# 4G_AD9.net
KiCad netlist of a schematic drawn in Altium Designer
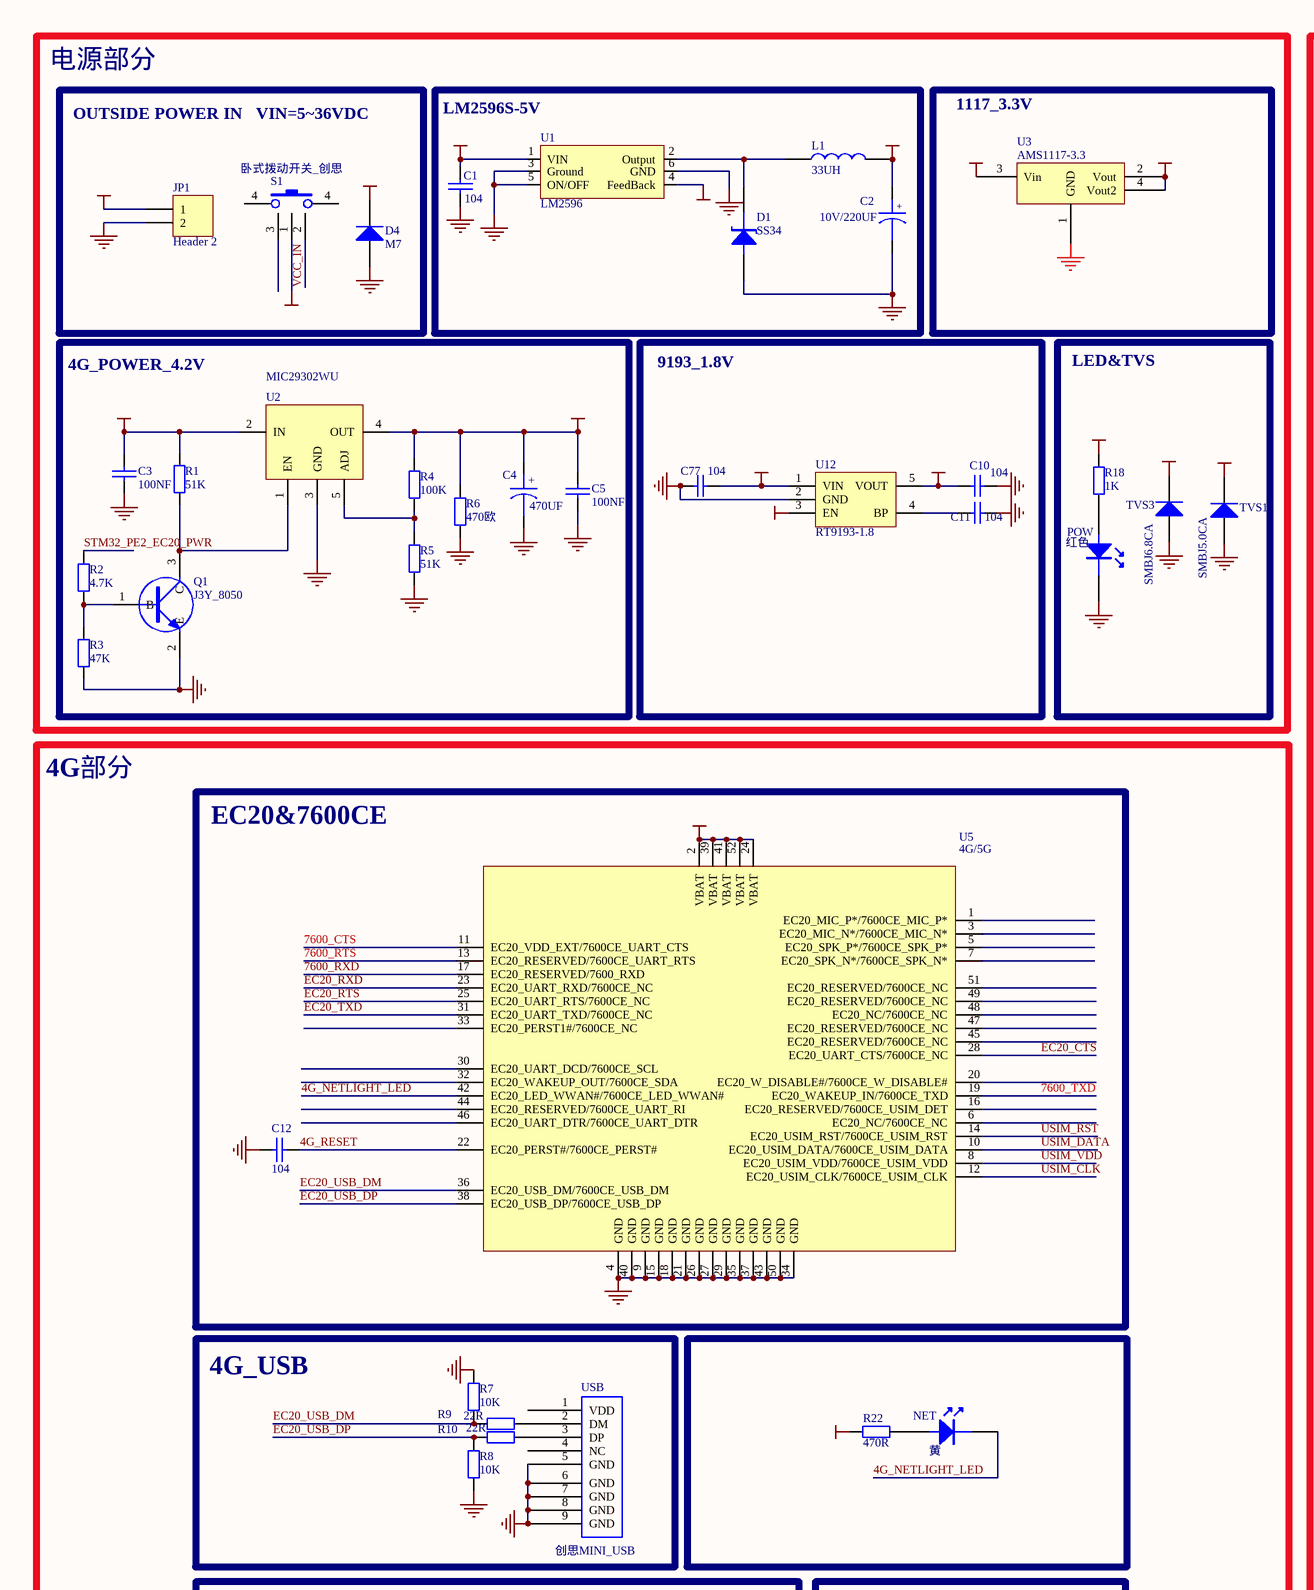
[diagram p0: 4G图传输原理图AD9.SchDoc, top left]
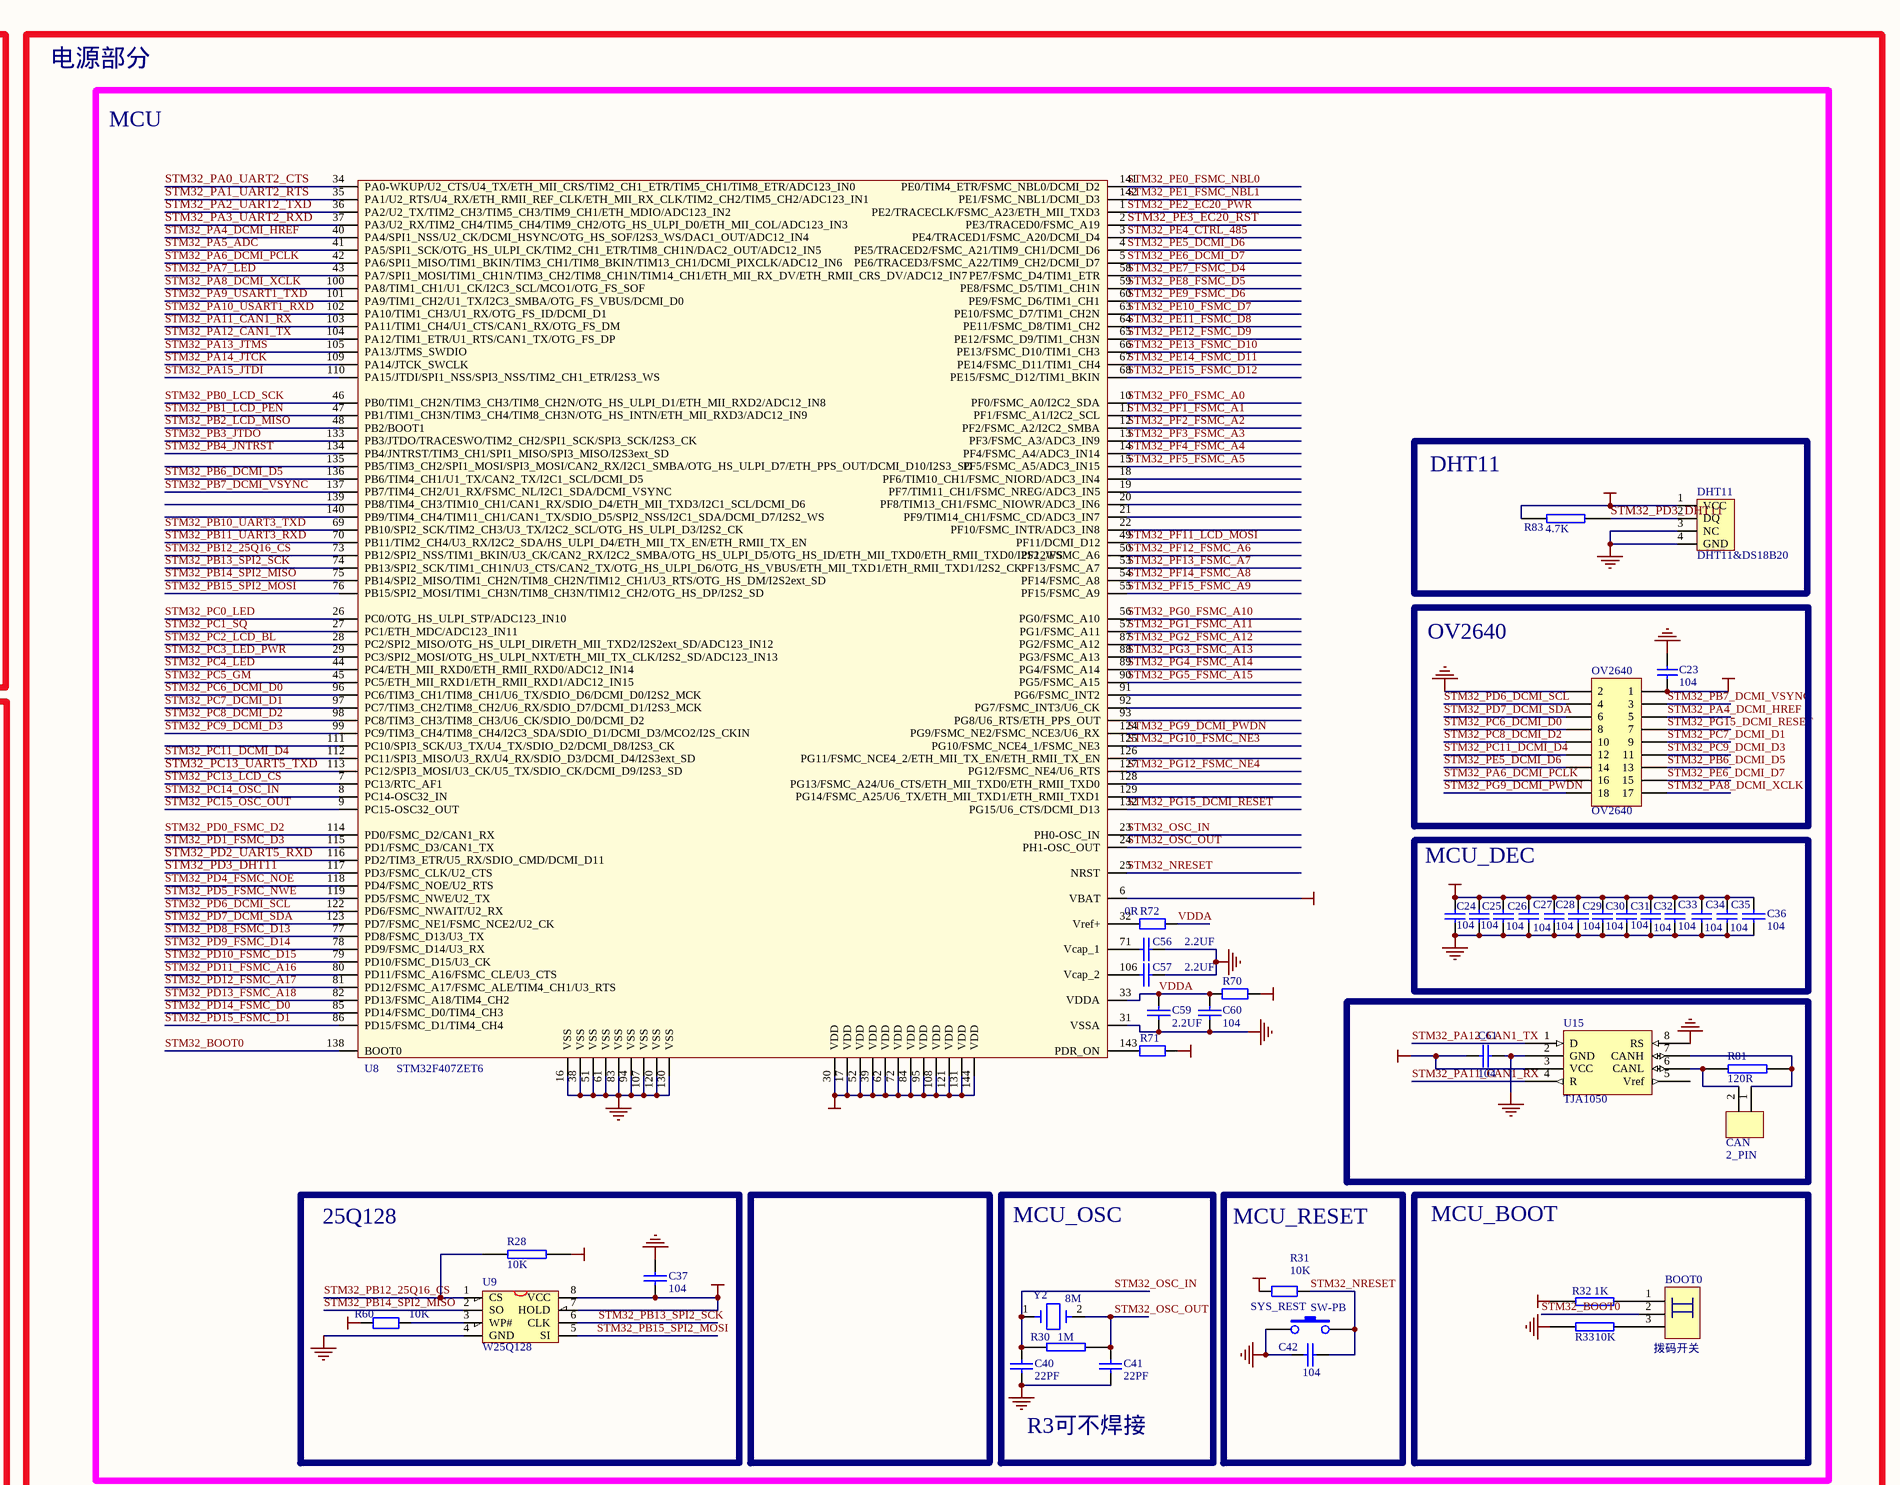
[diagram p1: 4G图传输原理图AD9.SchDoc, top right]
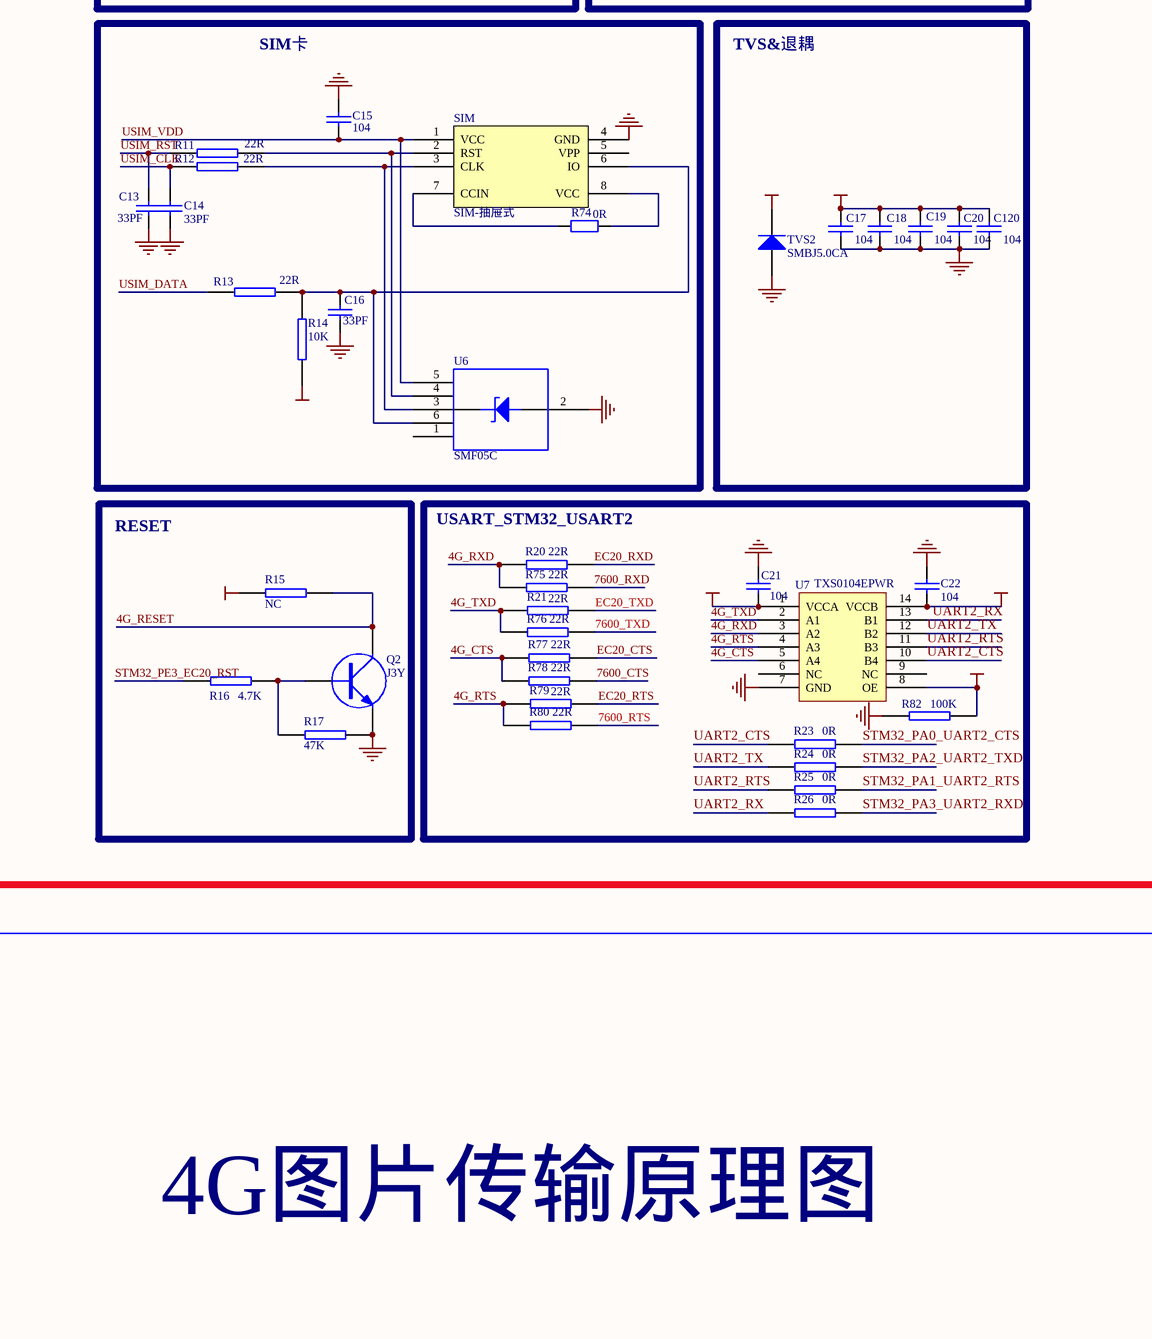
[diagram p2: 4G图传输原理图AD9.SchDoc, bottom left]
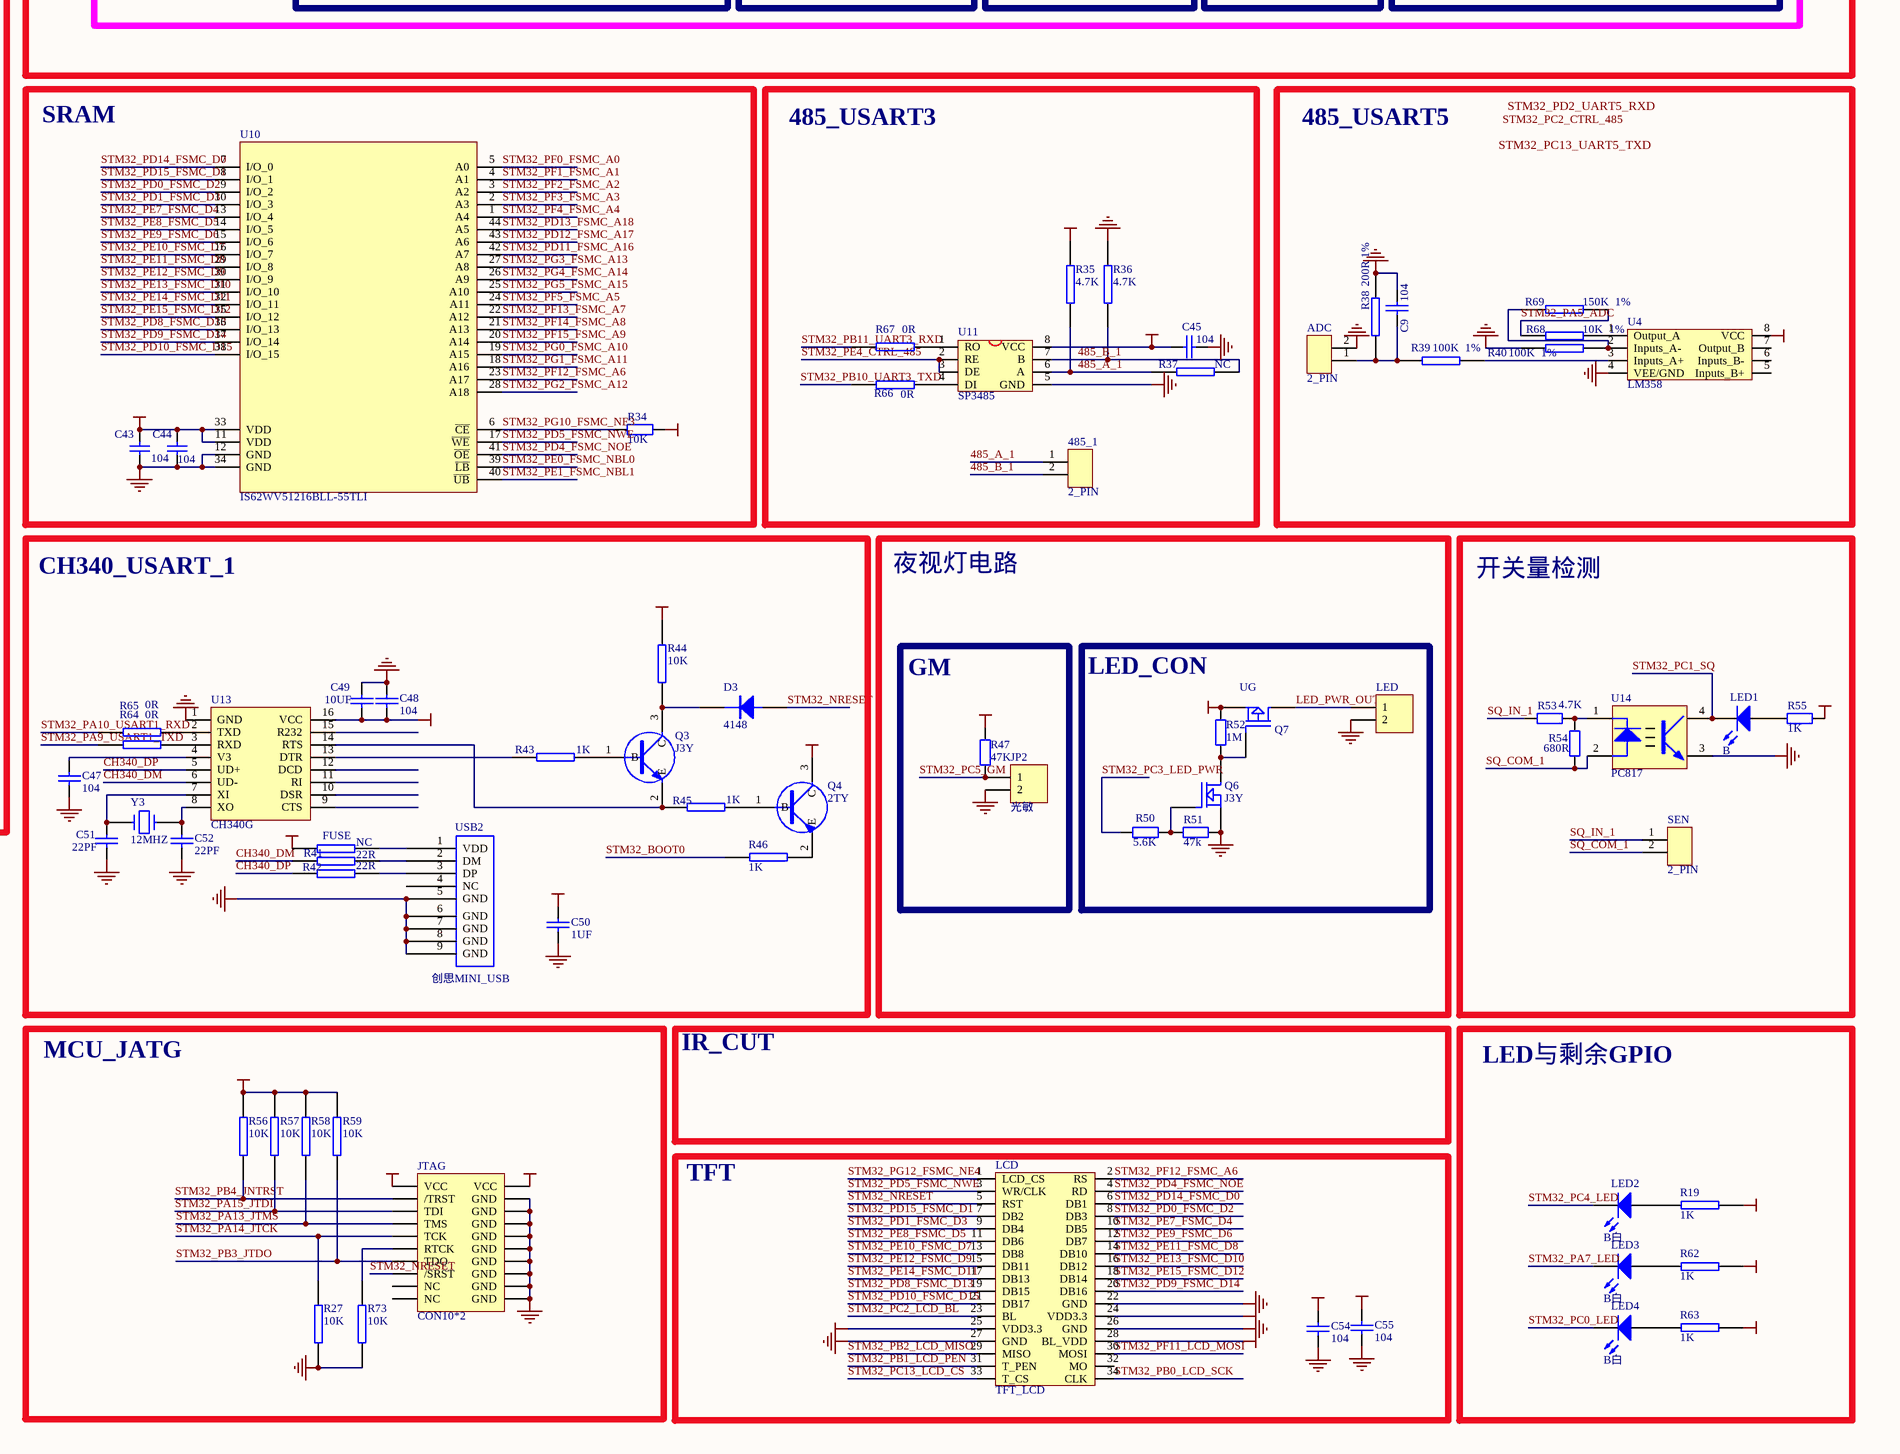
[diagram p3: 4G图传输原理图AD9.SchDoc, bottom right]

(export (version "E")
  (design (tool "Eeschema 10.0.6"))
  (components
    (comp (ref "485_1") (value "2_PIN") (footprint "5mm间距蓝色立式端子2P") (libsource (lib "") (part "2_PIN_1")))
    (comp (ref "ADC") (value "2_PIN") (footprint "5mm间距蓝色立式端子2P") (libsource (lib "*") (part "2_PIN")))
    (comp (ref "BOOT0") (value "拨码开关") (footprint "创思水墨屏拨码开关") (libsource (lib "常用元件") (part "创思水墨屏拨码开关")))
    (comp (ref "C1")
      (value "104")
      (footprint "C_0805_创思")
      (description "Capacitor")
      (libsource (lib "*") (part "CAP"))
    )
    (comp (ref "C2")
      (value "10V/220UF")
      (footprint "C_220UF/50V")
      (description "Capacitor")
      (libsource (lib "*") (part "PCAP"))
    )
    (comp (ref "C3")
      (value "100NF")
      (footprint "C_0805_创思")
      (description "Capacitor")
      (libsource (lib "*") (part "CAP"))
    )
    (comp (ref "C4")
      (value "470UF")
      (footprint "470UF_贴片电容")
      (description "Capacitor")
      (libsource (lib "*") (part "100UF/16V"))
    )
    (comp (ref "C5")
      (value "100NF")
      (footprint "C_0805_创思")
      (description "Capacitor")
      (libsource (lib "*") (part "CAP"))
    )
    (comp (ref "C9")
      (value "104")
      (footprint "C_0805_创思")
      (description "Capacitor")
      (libsource (lib "SCH总库") (part "CAP"))
    )
    (comp (ref "C10")
      (value "104")
      (footprint "C_0805_创思")
      (description "Capacitor")
      (fields (field (name "Comment") "Cap") (field (name "PUBLISHER") "Altium Limited"))
      (libsource (lib "*") (part "Cap"))
    )
    (comp (ref "C11")
      (value "104")
      (footprint "C_0805_创思")
      (description "Capacitor")
      (fields (field (name "Comment") "Cap") (field (name "PUBLISHER") "Altium Limited"))
      (libsource (lib "*") (part "Cap"))
    )
    (comp (ref "C12")
      (value "104")
      (footprint "C_0805_创思")
      (description "Capacitor")
      (libsource (lib "*") (part "CAP"))
    )
    (comp (ref "C13")
      (value "33PF")
      (footprint "C_0805_创思")
      (description "Capacitor")
      (libsource (lib "*") (part "CAP"))
    )
    (comp (ref "C14")
      (value "33PF")
      (footprint "C_0805_创思")
      (description "Capacitor")
      (libsource (lib "*") (part "CAP"))
    )
    (comp (ref "C15")
      (value "104")
      (footprint "C_0805_创思")
      (description "Capacitor")
      (libsource (lib "*") (part "CAP"))
    )
    (comp (ref "C16")
      (value "33PF")
      (footprint "C_0805_创思")
      (description "Capacitor")
      (libsource (lib "*") (part "CAP"))
    )
    (comp (ref "C17")
      (value "104")
      (footprint "C_0805_创思")
      (description "Capacitor")
      (libsource (lib "*") (part "CAP"))
    )
    (comp (ref "C18")
      (value "104")
      (footprint "C_0805_创思")
      (description "Capacitor")
      (libsource (lib "*") (part "CAP"))
    )
    (comp (ref "C19")
      (value "104")
      (footprint "C_0805_创思")
      (description "Capacitor")
      (libsource (lib "*") (part "CAP"))
    )
    (comp (ref "C20")
      (value "104")
      (footprint "C_0805_创思")
      (description "Capacitor")
      (libsource (lib "*") (part "CAP"))
    )
    (comp (ref "C21")
      (value "104")
      (footprint "C_0805_创思")
      (description "Capacitor")
      (libsource (lib "LXKJSJ") (part "CAP"))
    )
    (comp (ref "C22")
      (value "104")
      (footprint "C_0805_创思")
      (description "Capacitor")
      (libsource (lib "LXKJSJ") (part "CAP"))
    )
    (comp (ref "C23") (value "104") (footprint "C_0805_创思") (libsource (lib "常用元件") (part "贴片电容")))
    (comp (ref "C24") (value "104") (footprint "C_0805_创思") (libsource (lib "常用元件") (part "贴片电容")))
    (comp (ref "C25") (value "104") (footprint "C_0805_创思") (libsource (lib "常用元件") (part "贴片电容")))
    (comp (ref "C26") (value "104") (footprint "C_0805_创思") (libsource (lib "常用元件") (part "贴片电容")))
    (comp (ref "C27") (value "104") (footprint "C_0805_创思") (libsource (lib "常用元件") (part "贴片电容")))
    (comp (ref "C28") (value "104") (footprint "C_0805_创思") (libsource (lib "常用元件") (part "贴片电容")))
    (comp (ref "C29") (value "104") (footprint "C_0805_创思") (libsource (lib "常用元件") (part "贴片电容")))
    (comp (ref "C30") (value "104") (footprint "C_0805_创思") (libsource (lib "常用元件") (part "贴片电容")))
    (comp (ref "C31") (value "104") (footprint "C_0805_创思") (libsource (lib "常用元件") (part "贴片电容")))
    (comp (ref "C32") (value "104") (footprint "C_0805_创思") (libsource (lib "常用元件") (part "贴片电容")))
    (comp (ref "C33") (value "104") (footprint "C_0805_创思") (libsource (lib "常用元件") (part "贴片电容")))
    (comp (ref "C34") (value "104") (footprint "C_0805_创思") (libsource (lib "常用元件") (part "贴片电容")))
    (comp (ref "C35") (value "104") (footprint "C_0805_创思") (libsource (lib "常用元件") (part "贴片电容")))
    (comp (ref "C36")
      (value "104")
      (footprint "C_0805_创思")
      (description "Capacitor")
      (libsource (lib "*") (part "CAP"))
    )
    (comp (ref "C37")
      (value "104")
      (footprint "C_0805_创思")
      (description "Capacitor")
      (libsource (lib "*") (part "CAP"))
    )
    (comp (ref "C40")
      (value "22PF")
      (footprint "C_0805_创思")
      (description "Capacitor")
      (libsource (lib "*") (part "CAP"))
    )
    (comp (ref "C41")
      (value "22PF")
      (footprint "C_0805_创思")
      (description "Capacitor")
      (libsource (lib "*") (part "CAP"))
    )
    (comp (ref "C42")
      (value "104")
      (footprint "C_0805_创思")
      (description "Capacitor")
      (libsource (lib "*") (part "CAP"))
    )
    (comp (ref "C43")
      (value "104")
      (footprint "C_0805_创思")
      (description "Capacitor")
      (fields (field (name "PUBLISHER") "Altium Limited"))
      (libsource (lib "*") (part "Cap"))
    )
    (comp (ref "C44")
      (value "104")
      (footprint "C_0805_创思")
      (description "Capacitor")
      (fields (field (name "PUBLISHER") "Altium Limited"))
      (libsource (lib "*") (part "Cap"))
    )
    (comp (ref "C45")
      (value "104")
      (footprint "C_0805_创思")
      (description "Capacitor")
      (libsource (lib "*") (part "CAP"))
    )
    (comp (ref "C47")
      (value "104")
      (footprint "C_0805_创思")
      (description "Capacitor")
      (libsource (lib "*") (part "CAP"))
    )
    (comp (ref "C48")
      (value "104")
      (footprint "C_0805_创思")
      (description "Capacitor")
      (libsource (lib "*") (part "CAP"))
    )
    (comp (ref "C49")
      (value "10UF")
      (footprint "C_0805_创思")
      (description "Capacitor")
      (libsource (lib "*") (part "CAP"))
    )
    (comp (ref "C50")
      (value "1UF")
      (footprint "C_0805_创思")
      (description "Capacitor")
      (libsource (lib "*") (part "CAP"))
    )
    (comp (ref "C51")
      (value "22PF")
      (footprint "C_0805_创思")
      (description "Capacitor")
      (libsource (lib "*") (part "CAP"))
    )
    (comp (ref "C52")
      (value "22PF")
      (footprint "C_0805_创思")
      (description "Capacitor")
      (libsource (lib "*") (part "CAP"))
    )
    (comp (ref "C54")
      (value "104")
      (footprint "C_0805_创思")
      (description "Capacitor")
      (libsource (lib "*") (part "CAP"))
    )
    (comp (ref "C55")
      (value "104")
      (footprint "C_0805_创思")
      (description "Capacitor")
      (libsource (lib "*") (part "CAP"))
    )
    (comp (ref "C56")
      (value "2.2UF")
      (footprint "C_0805_创思")
      (description "Capcitor")
      (libsource (lib "LXKJSJ") (part "CAP"))
    )
    (comp (ref "C57")
      (value "2.2UF")
      (footprint "C_0805_创思")
      (description "Capcitor")
      (libsource (lib "LXKJSJ") (part "CAP"))
    )
    (comp (ref "C59")
      (value "2.2UF")
      (footprint "C_0805_创思")
      (description "Capcitor")
      (libsource (lib "LXKJSJ") (part "CAP"))
    )
    (comp (ref "C60")
      (value "104")
      (footprint "C_0805_创思")
      (description "Capcitor")
      (libsource (lib "LXKJSJ") (part "CAP"))
    )
    (comp (ref "C61")
      (value "104")
      (footprint "C_0805_创思")
      (description "Capacitor")
      (libsource (lib "*") (part "CAP"))
    )
    (comp (ref "C77")
      (value "104")
      (footprint "C_0805_创思")
      (description "Capacitor")
      (fields (field (name "Comment") "Cap") (field (name "PUBLISHER") "Altium Limited"))
      (libsource (lib "*") (part "Cap"))
    )
    (comp (ref "C120")
      (value "104")
      (footprint "C_0805_创思")
      (description "Capacitor")
      (libsource (lib "*") (part "CAP"))
    )
    (comp (ref "CAN") (value "2_PIN") (footprint "5mm间距蓝色立式端子2P") (libsource (lib "常用元件") (part "2_PIN")))
    (comp (ref "D1") (value "SS34") (footprint "5822") (libsource (lib "*") (part "TVS")))
    (comp (ref "D3") (value "4148") (footprint "4148") (libsource (lib "*") (part "DIDOE")))
    (comp (ref "D4")
      (value "M7")
      (footprint "5822")
      (description "Default Diode")
      (fields (field (name "PUBLISHER") "Altium Limited"))
      (libsource (lib "*") (part "Diode"))
    )
    (comp (ref "DHT11")
      (value "DHT11&DS18B20")
      (footprint "DHT11")
      (description "数字温湿度传感器")
      (libsource (lib "STM32F429_F746") (part "DHT11"))
    )
    (comp (ref "FUSE") (value "NC") (footprint "R_0805_创思") (libsource (lib "*") (part "RES2")))
    (comp (ref "JP1")
      (value "Header 2")
      (footprint "电源_卧")
      (description "Header, 2-Pin")
      (fields (field (name "PUBLISHER") "Altium Limited"))
      (libsource (lib "*") (part "Header 2"))
    )
    (comp (ref "JP2")
      (value "光敏")
      (footprint "插件光敏电阻")
      (description "Header, 2-Pin")
      (fields (field (name "PUBLISHER") "Altium Limited"))
      (libsource (lib "Miscellaneous Connectors") (part "Header 2"))
    )
    (comp (ref "JTAG")
      (value "CON10*2")
      (footprint "JTAG_创思")
      (description "Connector")
      (libsource (lib "*") (part "CON10*2"))
    )
    (comp (ref "L1") (value "33UH") (footprint "100UH插件功率电感") (libsource (lib "*") (part "INDUCTOR1")))
    (comp (ref "LCD") (value "TFT_LCD") (footprint "TFT_LCD") (libsource (lib "WARSHIP") (part "TFT_LCD")))
    (comp (ref "LED")
      (value "+ -")
      (footprint "HDR1X2")
      (description "Header, 2-Pin")
      (fields (field (name "PUBLISHER") "Altium Limited"))
      (libsource (lib "Miscellaneous Connectors") (part "Header 2"))
    )
    (comp (ref "LED1") (value "B") (footprint "D_0805_创思") (libsource (lib "常用元件") (part "发光二极管")))
    (comp (ref "LED2") (value "B白") (footprint "D_0805_创思") (libsource (lib "常用元件") (part "发光二极管")))
    (comp (ref "LED3") (value "B白") (footprint "D_0805_创思") (libsource (lib "常用元件") (part "发光二极管")))
    (comp (ref "LED4") (value "B白") (footprint "D_0805_创思") (libsource (lib "常用元件") (part "发光二极管")))
    (comp (ref "NET") (value "黄") (footprint "D_0805_创思") (libsource (lib "*") (part "LED")))
    (comp (ref "OV2640")
      (value "OV2640")
      (footprint "OV2640模块_弯角")
      (description "Header, 9-Pin, Dual row")
      (fields (field (name "PUBLISHER") "Altium Limited"))
      (libsource (lib "Miscellaneous Connectors") (part "Header 9X2"))
    )
    (comp (ref "POW") (value "红色") (footprint "D_0805_创思") (libsource (lib "*") (part "LED")))
    (comp (ref "Q1") (value "J3Y_8050") (footprint "J3Y_8050") (libsource (lib "*") (part "J3Y_8050")))
    (comp (ref "Q2")
      (value "J3Y")
      (footprint "J3Y_8050")
      (description "NPN Transistor")
      (libsource (lib "*") (part "NPN"))
    )
    (comp (ref "Q3") (value "J3Y") (footprint "J3Y_8050") (libsource (lib "*") (part "J3Y_8050")))
    (comp (ref "Q4") (value "2TY") (footprint "J3Y_8050") (libsource (lib "常用元件") (part "8550")))
    (comp (ref "Q6")
      (value "J3Y")
      (footprint "SOT23&SOT723")
      (description "MOSFET N")
      (libsource (lib "SCH库") (part "MOSFET N"))
    )
    (comp (ref "Q7") (value "UG") (footprint "SOT-23") (libsource (lib "Add_SCH") (part "AO3401")))
    (comp (ref "R1")
      (value "51K")
      (footprint "R_0805_创思")
      (description "Resistor")
      (fields (field (name "PUBLISHER") "*"))
      (libsource (lib "*") (part "Res2"))
    )
    (comp (ref "R2")
      (value "4.7K")
      (footprint "R_0805_创思")
      (description "Resistor")
      (fields (field (name "PUBLISHER") "*"))
      (libsource (lib "") (part "Res2_1"))
    )
    (comp (ref "R3")
      (value "47K")
      (footprint "R_0805_创思")
      (description "Resistor")
      (fields (field (name "PUBLISHER") "*"))
      (libsource (lib "*") (part "Res2"))
    )
    (comp (ref "R4")
      (value "100K")
      (footprint "R_0805_创思")
      (description "Resistor")
      (fields (field (name "PUBLISHER") "*"))
      (libsource (lib "*") (part "Res2"))
    )
    (comp (ref "R5")
      (value "51K")
      (footprint "R_0805_创思")
      (description "Resistor")
      (fields (field (name "PUBLISHER") "*"))
      (libsource (lib "*") (part "Res2"))
    )
    (comp (ref "R6")
      (value "470欧")
      (footprint "R_0805_创思")
      (description "Resistor")
      (fields (field (name "PUBLISHER") "*"))
      (libsource (lib "*") (part "Res2"))
    )
    (comp (ref "R7")
      (value "10K")
      (footprint "R_0805_创思")
      (description "Resistor")
      (fields (field (name "PUBLISHER") "*"))
      (libsource (lib "") (part "Res2_1"))
    )
    (comp (ref "R8")
      (value "10K")
      (footprint "R_0805_创思")
      (description "Resistor")
      (fields (field (name "PUBLISHER") "*"))
      (libsource (lib "") (part "Res2_1"))
    )
    (comp (ref "R9")
      (value "22R")
      (footprint "R_0805_创思")
      (description "Resistor")
      (fields (field (name "PUBLISHER") "*"))
      (libsource (lib "") (part "Res2_2"))
    )
    (comp (ref "R10")
      (value "22R")
      (footprint "R_0805_创思")
      (description "Resistor")
      (fields (field (name "PUBLISHER") "*"))
      (libsource (lib "") (part "Res2_2"))
    )
    (comp (ref "R11") (value "22R") (footprint "R_0805_创思") (libsource (lib "*") (part "RES2")))
    (comp (ref "R12") (value "22R") (footprint "R_0805_创思") (libsource (lib "*") (part "RES2")))
    (comp (ref "R13") (value "22R") (footprint "R_0805_创思") (libsource (lib "*") (part "RES2")))
    (comp (ref "R14") (value "10K") (footprint "R_0805_创思") (libsource (lib "*") (part "RES2")))
    (comp (ref "R15") (value "NC") (footprint "R_0805_创思") (libsource (lib "*") (part "RES2")))
    (comp (ref "R16") (value "4.7K") (footprint "R_0805_创思") (libsource (lib "*") (part "RES2")))
    (comp (ref "R17") (value "47K") (footprint "R_0805_创思") (libsource (lib "*") (part "RES2")))
    (comp (ref "R18")
      (value "1K")
      (footprint "R_0805_创思")
      (description "Resistor")
      (fields (field (name "PUBLISHER") "*"))
      (libsource (lib "") (part "Res2_1"))
    )
    (comp (ref "R19") (value "1K") (footprint "R_0805_创思") (libsource (lib "*") (part "RES2")))
    (comp (ref "R20") (value "22R") (footprint "R_0805_创思") (libsource (lib "*") (part "RES2")))
    (comp (ref "R21") (value "22R") (footprint "R_0805_创思") (libsource (lib "*") (part "RES2")))
    (comp (ref "R22")
      (value "470R")
      (footprint "R_0805_创思")
      (description "Resistor")
      (fields (field (name "PUBLISHER") "*"))
      (libsource (lib "") (part "Res2_2"))
    )
    (comp (ref "R23") (value "0R") (footprint "R_0805_创思") (libsource (lib "*") (part "RES2")))
    (comp (ref "R24") (value "0R") (footprint "R_0805_创思") (libsource (lib "*") (part "RES2")))
    (comp (ref "R25") (value "0R") (footprint "R_0805_创思") (libsource (lib "*") (part "RES2")))
    (comp (ref "R26") (value "0R") (footprint "R_0805_创思") (libsource (lib "*") (part "RES2")))
    (comp (ref "R27") (value "10K") (footprint "R_0805_创思") (libsource (lib "*") (part "RES2")))
    (comp (ref "R28") (value "10K") (footprint "R_0805_创思") (libsource (lib "*") (part "RES2")))
    (comp (ref "R30") (value "1M") (footprint "R_0805_创思") (libsource (lib "*") (part "RES2")))
    (comp (ref "R31")
      (value "10K")
      (footprint "R_0805_创思")
      (description "Resistor")
      (fields (field (name "PUBLISHER") "*"))
      (libsource (lib "") (part "Res2_3"))
    )
    (comp (ref "R32") (value "1K") (footprint "R_0805_创思") (libsource (lib "*") (part "RES2")))
    (comp (ref "R33") (value "10K") (footprint "R_0805_创思") (libsource (lib "*") (part "RES2")))
    (comp (ref "R34")
      (value "10K")
      (footprint "R_0805_创思")
      (description "Resistor")
      (libsource (lib "") (part "Res2_1"))
    )
    (comp (ref "R35") (value "4.7K") (footprint "R_0805_创思") (libsource (lib "*") (part "RES2")))
    (comp (ref "R36") (value "4.7K") (footprint "R_0805_创思") (libsource (lib "*") (part "RES2")))
    (comp (ref "R37") (value "NC") (footprint "R_0805_创思") (libsource (lib "*") (part "RES2")))
    (comp (ref "R38") (value "200R 1%") (footprint "R_0805_创思") (libsource (lib "*") (part "RES2")))
    (comp (ref "R39") (value "100K  1%") (footprint "R_0805_创思") (libsource (lib "*") (part "RES2")))
    (comp (ref "R40") (value "100K  1%") (footprint "R_0805_创思") (libsource (lib "*") (part "RES2")))
    (comp (ref "R41") (value "22R") (footprint "R_0805_创思") (libsource (lib "*") (part "RES2")))
    (comp (ref "R42") (value "22R") (footprint "R_0805_创思") (libsource (lib "*") (part "RES2")))
    (comp (ref "R43") (value "1K") (footprint "R_0805_创思") (libsource (lib "*") (part "RES2")))
    (comp (ref "R44") (value "10K") (footprint "R_0805_创思") (libsource (lib "*") (part "RES2")))
    (comp (ref "R45") (value "1K") (footprint "R_0805_创思") (libsource (lib "*") (part "RES2")))
    (comp (ref "R46") (value "1K") (footprint "R_0805_创思") (libsource (lib "*") (part "RES2")))
    (comp (ref "R47")
      (value "47K")
      (footprint "R_0805_创思")
      (description "Resistor")
      (fields (field (name "PUBLISHER") "Altium Limited"))
      (libsource (lib "Miscellaneous Devices") (part "Res2"))
    )
    (comp (ref "R50")
      (value "5.6K")
      (footprint "R_0805_创思")
      (description "Resistor")
      (fields (field (name "PUBLISHER") "Altium Limited"))
      (libsource (lib "") (part "Res2_1"))
    )
    (comp (ref "R51")
      (value "47k")
      (footprint "R_0805_创思")
      (description "Resistor")
      (fields (field (name "PUBLISHER") "Altium Limited"))
      (libsource (lib "") (part "Res2_1"))
    )
    (comp (ref "R52")
      (value "1M")
      (footprint "R_0805_创思")
      (description "Resistor")
      (fields (field (name "PUBLISHER") "Altium Limited"))
      (libsource (lib "") (part "Res2_3"))
    )
    (comp (ref "R53")
      (value "4.7K")
      (footprint "R_0805_创思")
      (description "Resistor")
      (fields (field (name "PUBLISHER") "Altium Limited"))
      (libsource (lib "") (part "Res2_2"))
    )
    (comp (ref "R54")
      (value "680R")
      (footprint "R_0805_创思")
      (description "Resistor")
      (fields (field (name "PUBLISHER") "Altium Limited"))
      (libsource (lib "Miscellaneous Devices") (part "Res2"))
    )
    (comp (ref "R55")
      (value "1K")
      (footprint "R_0805_创思")
      (description "Resistor")
      (fields (field (name "PUBLISHER") "Altium Limited"))
      (libsource (lib "") (part "Res2_1"))
    )
    (comp (ref "R56") (value "10K") (footprint "R_0805_创思") (libsource (lib "*") (part "RES2")))
    (comp (ref "R57") (value "10K") (footprint "R_0805_创思") (libsource (lib "*") (part "RES2")))
    (comp (ref "R58") (value "10K") (footprint "R_0805_创思") (libsource (lib "*") (part "RES2")))
    (comp (ref "R59") (value "10K") (footprint "R_0805_创思") (libsource (lib "*") (part "RES2")))
    (comp (ref "R60")
      (value "10K")
      (footprint "R_0805_创思")
      (description "Resistor")
      (fields (field (name "PUBLISHER") "Altium Limited"))
      (libsource (lib "") (part "Res2_1"))
    )
    (comp (ref "R62") (value "1K") (footprint "R_0805_创思") (libsource (lib "*") (part "RES2")))
    (comp (ref "R63") (value "1K") (footprint "R_0805_创思") (libsource (lib "*") (part "RES2")))
    (comp (ref "R64") (value "0R") (footprint "R_0805_创思") (libsource (lib "*") (part "RES2")))
    (comp (ref "R65") (value "0R") (footprint "R_0805_创思") (libsource (lib "*") (part "RES2")))
    (comp (ref "R66") (value "0R") (footprint "R_0805_创思") (libsource (lib "*") (part "RES2")))
    (comp (ref "R67") (value "0R") (footprint "R_0805_创思") (libsource (lib "*") (part "RES2")))
    (comp (ref "R68") (value "10K  1%") (footprint "R_0805_创思") (libsource (lib "*") (part "RES2")))
    (comp (ref "R69") (value "150K  1%") (footprint "R_0805_创思") (libsource (lib "*") (part "RES2")))
    (comp (ref "R70")
      (value "0R")
      (footprint "R_0805_创思")
      (description "Resistor")
      (fields (field (name "PUBLISHER") "Altium Limited"))
      (libsource (lib "") (part "Res2_2"))
    )
    (comp (ref "R71")
      (value "0R")
      (footprint "R_0805_创思")
      (description "Resistor")
      (fields (field (name "PUBLISHER") "Altium Limited"))
      (libsource (lib "") (part "Res2_2"))
    )
    (comp (ref "R72")
      (value "0R")
      (footprint "R_0805_创思")
      (description "Resistor")
      (fields (field (name "PUBLISHER") "Altium Limited"))
      (libsource (lib "") (part "Res2_2"))
    )
    (comp (ref "R73") (value "10K") (footprint "R_0805_创思") (libsource (lib "*") (part "RES2")))
    (comp (ref "R74")
      (value "0R")
      (footprint "R_0805_创思")
      (description "Resistor")
      (fields (field (name "PUBLISHER") "*"))
      (libsource (lib "") (part "Res2_2"))
    )
    (comp (ref "R75") (value "22R") (footprint "R_0805_创思") (libsource (lib "*") (part "RES2")))
    (comp (ref "R76") (value "22R") (footprint "R_0805_创思") (libsource (lib "*") (part "RES2")))
    (comp (ref "R77") (value "22R") (footprint "R_0805_创思") (libsource (lib "*") (part "RES2")))
    (comp (ref "R78") (value "22R") (footprint "R_0805_创思") (libsource (lib "*") (part "RES2")))
    (comp (ref "R79") (value "22R") (footprint "R_0805_创思") (libsource (lib "*") (part "RES2")))
    (comp (ref "R80") (value "22R") (footprint "R_0805_创思") (libsource (lib "*") (part "RES2")))
    (comp (ref "R81") (value "120R") (footprint "R_0805_创思") (libsource (lib "*") (part "RES2")))
    (comp (ref "R82") (value "100K") (footprint "R_0805_创思") (libsource (lib "*") (part "RES2")))
    (comp (ref "R83") (value "4.7K") (footprint "R_0805_创思") (libsource (lib "*") (part "RES2")))
    (comp (ref "S1") (value "卧式拨动开关_创思") (footprint "卧式拨动开关_创思") (libsource (lib "常用元件") (part "卧式拨动开关_创思")))
    (comp (ref "SEN") (value "2_PIN") (footprint "5mm间距蓝色立式端子2P") (libsource (lib "") (part "2_PIN_1")))
    (comp (ref "SIM") (value "SIM-抽屉式") (footprint "SIMCARD8") (libsource (lib "*") (part "SIM-抽屉式")))
    (comp (ref "SYS_REST") (value "SW-PB") (footprint "BTN") (libsource (lib "*") (part "SW-PB")))
    (comp (ref "TVS1")
      (value "SMBJ5.0CA")
      (footprint "IN4007")
      (description "Default Diode")
      (fields (field (name "PUBLISHER") "Altium Limited"))
      (libsource (lib "*") (part "Diode"))
    )
    (comp (ref "TVS2")
      (value "SMBJ5.0CA")
      (footprint "IN4007")
      (description "Default Diode")
      (fields (field (name "PUBLISHER") "Altium Limited"))
      (libsource (lib "*") (part "Diode"))
    )
    (comp (ref "TVS3")
      (value "SMBJ6.8CA")
      (footprint "IN4007")
      (description "Default Diode")
      (fields (field (name "PUBLISHER") "Altium Limited"))
      (libsource (lib "*") (part "Diode"))
    )
    (comp (ref "U1") (value "LM2596") (footprint "LM2576") (libsource (lib "*") (part "LM2567")))
    (comp (ref "U2") (value "MIC29302WU") (footprint "29302") (libsource (lib "*") (part "MIC29302WU")))
    (comp (ref "U3") (value "AMS1117-3.3") (footprint "SPX1117") (libsource (lib "*") (part "AMS1117-3.3")))
    (comp (ref "U4")
      (value "LM358")
      (footprint "SOP_8_N")
      (libsource (lib "STM32F407+WIFI8801+摄像头硬件设计") (part "LM358"))
    )
    (comp (ref "U5")
      (value "4G/5G")
      (footprint "3G/4G模块_PCI")
      (libsource (lib "*") (part "EC20&7600CE_MINI_PCI"))
    )
    (comp (ref "U6") (value "SMF05C") (footprint "SOT-363") (libsource (lib "*") (part "SMF05C")))
    (comp (ref "U7")
      (value "TXS0104EPWR")
      (footprint "TSSOP-14N")
      (libsource (lib "Add_SCH") (part "TXS0104"))
    )
    (comp (ref "U8")
      (value "STM32F407ZET6")
      (footprint "LQFP144")
      (libsource (lib "EXPLORER") (part "STM32F407ZET6"))
    )
    (comp (ref "U9")
      (value "W25Q128")
      (footprint "SOIC-8")
      (description "W25X16;SST25VF016;MX25L1605")
      (libsource (lib "EXPLORER") (part "W25X16"))
    )
    (comp (ref "U10")
      (value "IS62WV51216BLL-55TLI")
      (footprint "TSOP44")
      (libsource (lib "STM32_DSO") (part "IS62WV51216BLL-55TLI"))
    )
    (comp (ref "U11") (value "SP3485") (footprint "SOP_8_N") (libsource (lib "*") (part "MAX3485")))
    (comp (ref "U12") (value "RT9193-1.8") (footprint "RT9193-33") (libsource (lib "*") (part "RT9193-33")))
    (comp (ref "U13") (value "CH340G") (footprint "SOP16") (libsource (lib "常用芯片") (part "CH340G")))
    (comp (ref "U14") (value "PC817") (footprint "PC817贴片") (libsource (lib "常用芯片") (part "PC817")))
    (comp (ref "U15") (value "TJA1050") (footprint "SOP-8") (libsource (lib "EXPLORER") (part "SN65HVD230D")))
    (comp (ref "USB") (value "创思MINI_USB") (footprint "创思MINI_USB") (libsource (lib "*") (part "创思MINI_USB")))
    (comp (ref "USB2")
      (value "创思MINI_USB")
      (footprint "创思MINI_USB")
      (libsource (lib "*") (part "创思MINI_USB"))
    )
    (comp (ref "Y2") (value "8M") (footprint "晶振2 - duplicate") (libsource (lib "*") (part "CRYTAL")))
    (comp (ref "Y3") (value "12MHZ") (footprint "晶振2 - duplicate") (libsource (lib "*") (part "晶振")))
  )
  (nets
    (net (code "1") (name "/4G_CTS") (class "Default")
      (node (ref "R77") (pin "2") (pinfunction "2_2") (pintype "passive"))
      (node (ref "R78") (pin "2") (pinfunction "2_2") (pintype "passive"))
      (node (ref "U7") (pin "5") (pinfunction "A4_5") (pintype "passive"))
    )
    (net (code "2") (name "/4G_NETLIGHT_LED") (class "Default")
      (node (ref "NET") (pin "2") (pinfunction "2_2") (pintype "passive"))
      (node (ref "U5") (pin "42") (pinfunction "EC20_LED_WWAN#/7600CE_LED_WWAN#_42") (pintype "passive"))
    )
    (net (code "3") (name "/4G_RESET") (class "Default")
      (node (ref "C12") (pin "1") (pinfunction "1_1") (pintype "passive"))
      (node (ref "Q2") (pin "3") (pinfunction "C_3") (pintype "passive"))
      (node (ref "R15") (pin "1") (pinfunction "1_1") (pintype "passive"))
      (node (ref "U5") (pin "22") (pinfunction "EC20_PERST#/7600CE_PERST#_22") (pintype "passive"))
    )
    (net (code "4") (name "/4G_RTS") (class "Default")
      (node (ref "R79") (pin "2") (pinfunction "2_2") (pintype "passive"))
      (node (ref "R80") (pin "2") (pinfunction "2_2") (pintype "passive"))
      (node (ref "U7") (pin "4") (pinfunction "A3_4") (pintype "passive"))
    )
    (net (code "5") (name "/4G_RXD") (class "Default")
      (node (ref "R20") (pin "2") (pinfunction "2_2") (pintype "passive"))
      (node (ref "R75") (pin "2") (pinfunction "2_2") (pintype "passive"))
      (node (ref "U7") (pin "3") (pinfunction "A2_3") (pintype "passive"))
    )
    (net (code "6") (name "/4G_TXD") (class "Default")
      (node (ref "R21") (pin "2") (pinfunction "2_2") (pintype "passive"))
      (node (ref "R76") (pin "2") (pinfunction "2_2") (pintype "passive"))
      (node (ref "U7") (pin "2") (pinfunction "A1_2") (pintype "passive"))
    )
    (net (code "7") (name "/485_A_1") (class "Default")
      (node (ref "485_1") (pin "1") (pinfunction "1_1") (pintype "passive"))
      (node (ref "R35") (pin "1") (pinfunction "1_1") (pintype "passive"))
      (node (ref "R37") (pin "1") (pinfunction "1_1") (pintype "passive"))
      (node (ref "U11") (pin "6") (pinfunction "A_6") (pintype "passive"))
    )
    (net (code "8") (name "/485_B_1") (class "Default")
      (node (ref "485_1") (pin "2") (pinfunction "2_2") (pintype "passive"))
      (node (ref "R36") (pin "1") (pinfunction "1_1") (pintype "passive"))
      (node (ref "R37") (pin "2") (pinfunction "2_2") (pintype "passive"))
      (node (ref "U11") (pin "7") (pinfunction "B_7") (pintype "passive"))
    )
    (net (code "9") (name "/7600_CTS") (class "Default")
      (node (ref "R78") (pin "1") (pinfunction "1_1") (pintype "passive"))
      (node (ref "U5") (pin "11") (pinfunction "EC20_VDD_EXT/7600CE_UART_CTS_11") (pintype "passive"))
    )
    (net (code "10") (name "/7600_RTS") (class "Default")
      (node (ref "R80") (pin "1") (pinfunction "1_1") (pintype "passive"))
      (node (ref "U5") (pin "13") (pinfunction "EC20_RESERVED/7600CE_UART_RTS_13") (pintype "passive"))
    )
    (net (code "11") (name "/7600_RXD") (class "Default")
      (node (ref "R75") (pin "1") (pinfunction "1_1") (pintype "passive"))
      (node (ref "U5") (pin "17") (pinfunction "EC20_RESERVED/7600_RXD_17") (pintype "passive"))
    )
    (net (code "12") (name "/7600_TXD") (class "Default")
      (node (ref "R76") (pin "1") (pinfunction "1_1") (pintype "passive"))
      (node (ref "U5") (pin "19") (pinfunction "EC20_WAKEUP_IN/7600CE_TXD_19") (pintype "passive"))
    )
    (net (code "13") (name "/CH340_DM") (class "Default")
      (node (ref "R41") (pin "2") (pinfunction "2_2") (pintype "passive"))
      (node (ref "U13") (pin "6") (pinfunction "UD-_6") (pintype "passive"))
    )
    (net (code "14") (name "/CH340_DP") (class "Default")
      (node (ref "R42") (pin "2") (pinfunction "2_2") (pintype "passive"))
      (node (ref "U13") (pin "5") (pinfunction "UD+_5") (pintype "passive"))
    )
    (net (code "15") (name "/EC20_CTS") (class "Default")
      (node (ref "R77") (pin "1") (pinfunction "1_1") (pintype "passive"))
      (node (ref "U5") (pin "28") (pinfunction "EC20_UART_CTS/7600CE_NC_28") (pintype "passive"))
    )
    (net (code "16") (name "/EC20_RTS") (class "Default")
      (node (ref "R79") (pin "1") (pinfunction "1_1") (pintype "passive"))
      (node (ref "U5") (pin "25") (pinfunction "EC20_UART_RTS/7600CE_NC_25") (pintype "passive"))
    )
    (net (code "17") (name "/EC20_RXD") (class "Default")
      (node (ref "R20") (pin "1") (pinfunction "1_1") (pintype "passive"))
      (node (ref "U5") (pin "23") (pinfunction "EC20_UART_RXD/7600CE_NC_23") (pintype "passive"))
    )
    (net (code "18") (name "/EC20_TXD") (class "Default")
      (node (ref "R21") (pin "1") (pinfunction "1_1") (pintype "passive"))
      (node (ref "U5") (pin "31") (pinfunction "EC20_UART_TXD/7600CE_NC_31") (pintype "passive"))
    )
    (net (code "19") (name "/EC20_USB_DM") (class "Default")
      (node (ref "R7") (pin "1") (pinfunction "1_1") (pintype "passive"))
      (node (ref "R9") (pin "2") (pinfunction "2_2") (pintype "passive"))
      (node (ref "U5") (pin "36") (pinfunction "EC20_USB_DM/7600CE_USB_DM_36") (pintype "passive"))
    )
    (net (code "20") (name "/EC20_USB_DP") (class "Default")
      (node (ref "R10") (pin "2") (pinfunction "2_2") (pintype "passive"))
      (node (ref "R8") (pin "2") (pinfunction "2_2") (pintype "passive"))
      (node (ref "U5") (pin "38") (pinfunction "EC20_USB_DP/7600CE_USB_DP_38") (pintype "passive"))
    )
    (net (code "21") (name "/LED_PWR_OUT") (class "Default")
      (node (ref "LED") (pin "1") (pinfunction "1_1") (pintype "passive"))
      (node (ref "Q7") (pin "3") (pinfunction "D_3") (pintype "passive"))
    )
    (net (code "22") (name "/SQ_COM_1") (class "Default")
      (node (ref "R54") (pin "2") (pinfunction "2_2") (pintype "passive"))
      (node (ref "SEN") (pin "2") (pinfunction "2_2") (pintype "passive"))
      (node (ref "U14") (pin "2") (pintype "passive"))
    )
    (net (code "23") (name "/SQ_IN_1") (class "Default")
      (node (ref "R53") (pin "2") (pinfunction "2_2") (pintype "passive"))
      (node (ref "SEN") (pin "1") (pinfunction "1_1") (pintype "passive"))
    )
    (net (code "24") (name "/STM32_BOOT0") (class "Default")
      (node (ref "BOOT0") (pin "2") (pinfunction "2_2") (pintype "passive"))
      (node (ref "R46") (pin "1") (pinfunction "1_1") (pintype "passive"))
      (node (ref "U8") (pin "138") (pinfunction "BOOT0_138") (pintype "passive"))
    )
    (net (code "25") (name "/STM32_NRESET") (class "Default")
      (node (ref "C42") (pin "1") (pinfunction "1_1") (pintype "passive"))
      (node (ref "D3") (pin "1") (pinfunction "1_1") (pintype "passive"))
      (node (ref "JTAG") (pin "15") (pinfunction "/SRST_15") (pintype "passive"))
      (node (ref "LCD") (pin "5") (pinfunction "RST_5") (pintype "passive"))
      (node (ref "R31") (pin "2") (pinfunction "2_2") (pintype "passive"))
      (node (ref "SYS_REST") (pin "2") (pinfunction "2_2") (pintype "passive"))
      (node (ref "U8") (pin "25") (pinfunction "NRST_25") (pintype "passive"))
    )
    (net (code "26") (name "/STM32_OSC_IN") (class "Default")
      (node (ref "C40") (pin "1") (pinfunction "1_1") (pintype "passive"))
      (node (ref "R30") (pin "1") (pinfunction "1_1") (pintype "passive"))
      (node (ref "U8") (pin "23") (pinfunction "PH0-OSC_IN_23") (pintype "passive"))
      (node (ref "Y2") (pin "1") (pinfunction "1_1") (pintype "passive"))
    )
    (net (code "27") (name "/STM32_OSC_OUT") (class "Default")
      (node (ref "C41") (pin "1") (pinfunction "1_1") (pintype "passive"))
      (node (ref "R30") (pin "2") (pinfunction "2_2") (pintype "passive"))
      (node (ref "U8") (pin "24") (pinfunction "PH1-OSC_OUT_24") (pintype "passive"))
      (node (ref "Y2") (pin "2") (pinfunction "2_2") (pintype "passive"))
    )
    (net (code "28") (name "/STM32_PA0_UART2_CTS") (class "Default")
      (node (ref "R23") (pin "1") (pinfunction "1_1") (pintype "passive"))
      (node (ref "U8") (pin "34") (pinfunction "PA0-WKUP/U2_CTS/U4_TX/ETH_MII_CRS/TIM2_CH1_ETR/TIM5_CH1/TIM8_ETR/ADC123_IN0_34") (pintype "passive"))
    )
    (net (code "29") (name "/STM32_PA1_UART2_RTS") (class "Default")
      (node (ref "R25") (pin "1") (pinfunction "1_1") (pintype "passive"))
      (node (ref "U8") (pin "35") (pinfunction "PA1/U2_RTS/U4_RX/ETH_RMII_REF_CLK/ETH_MII_RX_CLK/TIM2_CH2/TIM5_CH2/ADC123_IN1_35") (pintype "passive"))
    )
    (net (code "30") (name "/STM32_PA2_UART2_TXD") (class "Default")
      (node (ref "R24") (pin "1") (pinfunction "1_1") (pintype "passive"))
      (node (ref "U8") (pin "36") (pinfunction "PA2/U2_TX/TIM2_CH3/TIM5_CH3/TIM9_CH1/ETH_MDIO/ADC123_IN2_36") (pintype "passive"))
    )
    (net (code "31") (name "/STM32_PA3_UART2_RXD") (class "Default")
      (node (ref "R26") (pin "1") (pinfunction "1_1") (pintype "passive"))
      (node (ref "U8") (pin "37") (pinfunction "PA3/U2_RX/TIM2_CH4/TIM5_CH4/TIM9_CH2/OTG_HS_ULPI_D0/ETH_MII_COL/ADC123_IN3_37") (pintype "passive"))
    )
    (net (code "32") (name "/STM32_PA4_DCMI_HREF") (class "Default")
      (node (ref "OV2640") (pin "5") (pinfunction "5_5") (pintype "passive"))
      (node (ref "U8") (pin "40") (pinfunction "PA4/SPI1_NSS/U2_CK/DCMI_HSYNC/OTG_HS_SOF/I2S3_WS/DAC1_OUT/ADC12_IN4_40") (pintype "passive"))
    )
    (net (code "33") (name "/STM32_PA5_ADC") (class "Default")
      (node (ref "R68") (pin "1") (pinfunction "1_1") (pintype "passive"))
      (node (ref "R69") (pin "1") (pinfunction "1_1") (pintype "passive"))
      (node (ref "U8") (pin "41") (pinfunction "PA5/SPI1_SCK/OTG_HS_ULPI_CK/TIM2_CH1_ETR/TIM8_CH1N/DAC2_OUT/ADC12_IN5_41") (pintype "passive"))
    )
    (net (code "34") (name "/STM32_PA6_DCMI_PCLK") (class "Default")
      (node (ref "OV2640") (pin "16") (pinfunction "16_16") (pintype "passive"))
      (node (ref "U8") (pin "42") (pinfunction "PA6/SPI1_MISO/TIM1_BKIN/TIM3_CH1/TIM8_BKIN/TIM13_CH1/DCMI_PIXCLK/ADC12_IN6_42") (pintype "passive"))
    )
    (net (code "35") (name "/STM32_PA7_LED") (class "Default")
      (node (ref "LED3") (pin "2") (pinfunction "K_2") (pintype "passive"))
      (node (ref "U8") (pin "43") (pinfunction "PA7/SPI1_MOSI/TIM1_CH1N/TIM3_CH2/TIM8_CH1N/TIM14_CH1/ETH_MII_RX_DV/ETH_RMII_CRS_DV/ADC12_IN7_43") (pintype "passive"))
    )
    (net (code "36") (name "/STM32_PA8_DCMI_XCLK") (class "Default")
      (node (ref "OV2640") (pin "17") (pinfunction "17_17") (pintype "passive"))
      (node (ref "U8") (pin "100") (pinfunction "PA8/TIM1_CH1/U1_CK/I2C3_SCL/MCO1/OTG_FS_SOF_100") (pintype "passive"))
    )
    (net (code "37") (name "/STM32_PA9_USART1_TXD") (class "Default")
      (node (ref "R64") (pin "2") (pinfunction "2_2") (pintype "passive"))
      (node (ref "U8") (pin "101") (pinfunction "PA9/TIM1_CH2/U1_TX/I2C3_SMBA/OTG_FS_VBUS/DCMI_D0_101") (pintype "passive"))
    )
    (net (code "38") (name "/STM32_PA10_USART1_RXD") (class "Default")
      (node (ref "R65") (pin "2") (pinfunction "2_2") (pintype "passive"))
      (node (ref "U8") (pin "102") (pinfunction "PA10/TIM1_CH3/U1_RX/OTG_FS_ID/DCMI_D1_102") (pintype "passive"))
    )
    (net (code "39") (name "/STM32_PA11_CAN1_RX") (class "Default")
      (node (ref "U15") (pin "4") (pinfunction "R_4") (pintype "output"))
      (node (ref "U8") (pin "103") (pinfunction "PA11/TIM1_CH4/U1_CTS/CAN1_RX/OTG_FS_DM_103") (pintype "passive"))
    )
    (net (code "40") (name "/STM32_PA12_CAN1_TX") (class "Default")
      (node (ref "U15") (pin "1") (pinfunction "D_1") (pintype "input"))
      (node (ref "U8") (pin "104") (pinfunction "PA12/TIM1_ETR/U1_RTS/CAN1_TX/OTG_FS_DP_104") (pintype "passive"))
    )
    (net (code "41") (name "/STM32_PA13_JTMS") (class "Default")
      (node (ref "JTAG") (pin "7") (pinfunction "TMS_7") (pintype "passive"))
      (node (ref "R58") (pin "1") (pinfunction "1_1") (pintype "passive"))
      (node (ref "U8") (pin "105") (pinfunction "PA13/JTMS_SWDIO_105") (pintype "passive"))
    )
    (net (code "42") (name "/STM32_PA14_JTCK") (class "Default")
      (node (ref "JTAG") (pin "9") (pinfunction "TCK_9") (pintype "passive"))
      (node (ref "R27") (pin "2") (pinfunction "2_2") (pintype "passive"))
      (node (ref "U8") (pin "109") (pinfunction "PA14/JTCK_SWCLK_109") (pintype "passive"))
    )
    (net (code "43") (name "/STM32_PA15_JTDI") (class "Default")
      (node (ref "JTAG") (pin "5") (pinfunction "TDI_5") (pintype "passive"))
      (node (ref "R57") (pin "1") (pinfunction "1_1") (pintype "passive"))
      (node (ref "U8") (pin "110") (pinfunction "PA15/JTDI/SPI1_NSS/SPI3_NSS/TIM2_CH1_ETR/I2S3_WS_110") (pintype "passive"))
    )
    (net (code "44") (name "/STM32_PB0_LCD_SCK") (class "Default")
      (node (ref "LCD") (pin "34") (pinfunction "CLK_34") (pintype "passive"))
      (node (ref "U8") (pin "46") (pinfunction "PB0/TIM1_CH2N/TIM3_CH3/TIM8_CH2N/OTG_HS_ULPI_D1/ETH_MII_RXD2/ADC12_IN8_46") (pintype "passive"))
    )
    (net (code "45") (name "/STM32_PB1_LCD_PEN") (class "Default")
      (node (ref "LCD") (pin "31") (pinfunction "T_PEN_31") (pintype "passive"))
      (node (ref "U8") (pin "47") (pinfunction "PB1/TIM1_CH3N/TIM3_CH4/TIM8_CH3N/OTG_HS_INTN/ETH_MII_RXD3/ADC12_IN9_47") (pintype "passive"))
    )
    (net (code "46") (name "/STM32_PB2_LCD_MISO") (class "Default")
      (node (ref "LCD") (pin "29") (pinfunction "MISO_29") (pintype "passive"))
      (node (ref "U8") (pin "48") (pinfunction "PB2/BOOT1_48") (pintype "passive"))
    )
    (net (code "47") (name "/STM32_PB3_JTDO") (class "Default")
      (node (ref "JTAG") (pin "13") (pinfunction "TDO_13") (pintype "passive"))
      (node (ref "R59") (pin "1") (pinfunction "1_1") (pintype "passive"))
      (node (ref "U8") (pin "133") (pinfunction "PB3/JTDO/TRACESWO/TIM2_CH2/SPI1_SCK/SPI3_SCK/I2S3_CK_133") (pintype "passive"))
    )
    (net (code "48") (name "/STM32_PB4_JNTRST") (class "Default")
      (node (ref "JTAG") (pin "3") (pinfunction "/TRST_3") (pintype "passive"))
      (node (ref "R56") (pin "1") (pinfunction "1_1") (pintype "passive"))
      (node (ref "U8") (pin "134") (pinfunction "PB4/JNTRST/TIM3_CH1/SPI1_MISO/SPI3_MISO/I2S3ext_SD_134") (pintype "passive"))
    )
    (net (code "49") (name "/STM32_PB6_DCMI_D5") (class "Default")
      (node (ref "OV2640") (pin "13") (pinfunction "13_13") (pintype "passive"))
      (node (ref "U8") (pin "136") (pinfunction "PB6/TIM4_CH1/U1_TX/CAN2_TX/I2C1_SCL/DCMI_D5_136") (pintype "passive"))
    )
    (net (code "50") (name "/STM32_PB7_DCMI_VSYNC") (class "Default")
      (node (ref "OV2640") (pin "3") (pinfunction "3_3") (pintype "passive"))
      (node (ref "U8") (pin "137") (pinfunction "PB7/TIM4_CH2/U1_RX/FSMC_NL/I2C1_SDA/DCMI_VSYNC_137") (pintype "passive"))
    )
    (net (code "51") (name "/STM32_PB10_UART3_TXD") (class "Default")
      (node (ref "R66") (pin "2") (pinfunction "2_2") (pintype "passive"))
      (node (ref "U8") (pin "69") (pinfunction "PB10/SPI2_SCK/TIM2_CH3/U3_TX/I2C2_SCL/OTG_HS_ULPI_D3/I2S2_CK_69") (pintype "passive"))
    )
    (net (code "52") (name "/STM32_PB11_UART3_RXD") (class "Default")
      (node (ref "R67") (pin "2") (pinfunction "2_2") (pintype "passive"))
      (node (ref "U8") (pin "70") (pinfunction "PB11/TIM2_CH4/U3_RX/I2C2_SDA/HS_ULPI_D4/ETH_MII_TX_EN/ETH_RMII_TX_EN_70") (pintype "passive"))
    )
    (net (code "53") (name "/STM32_PB12_25Q16_CS") (class "Default")
      (node (ref "R28") (pin "2") (pinfunction "2_2") (pintype "passive"))
      (node (ref "U8") (pin "73") (pinfunction "PB12/SPI2_NSS/TIM1_BKIN/U3_CK/CAN2_RX/I2C2_SMBA/OTG_HS_ULPI_D5/OTG_HS_ID/ETH_MII_TXD0/ETH_RMII_TXD0/I2S2_WS_73") (pintype "passive"))
      (node (ref "U9") (pin "1") (pinfunction "CS_1") (pintype "passive"))
    )
    (net (code "54") (name "/STM32_PB13_SPI2_SCK") (class "Default")
      (node (ref "U8") (pin "74") (pinfunction "PB13/SPI2_SCK/TIM1_CH1N/U3_CTS/CAN2_TX/OTG_HS_ULPI_D6/OTG_HS_VBUS/ETH_MII_TXD1/ETH_RMII_TXD1/I2S2_CK_74") (pintype "passive"))
      (node (ref "U9") (pin "6") (pinfunction "CLK_6") (pintype "passive"))
    )
    (net (code "55") (name "/STM32_PB14_SPI2_MISO") (class "Default")
      (node (ref "U8") (pin "75") (pinfunction "PB14/SPI2_MISO/TIM1_CH2N/TIM8_CH2N/TIM12_CH1/U3_RTS/OTG_HS_DM/I2S2ext_SD_75") (pintype "passive"))
      (node (ref "U9") (pin "2") (pinfunction "SO_2") (pintype "passive"))
    )
    (net (code "56") (name "/STM32_PB15_SPI2_MOSI") (class "Default")
      (node (ref "U8") (pin "76") (pinfunction "PB15/SPI2_MOSI/TIM1_CH3N/TIM8_CH3N/TIM12_CH2/OTG_HS_DP/I2S2_SD_76") (pintype "passive"))
      (node (ref "U9") (pin "5") (pinfunction "SI_5") (pintype "passive"))
    )
    (net (code "57") (name "/STM32_PC0_LED") (class "Default")
      (node (ref "LED4") (pin "2") (pinfunction "K_2") (pintype "passive"))
      (node (ref "U8") (pin "26") (pinfunction "PC0/OTG_HS_ULPI_STP/ADC123_IN10_26") (pintype "passive"))
    )
    (net (code "58") (name "/STM32_PC1_SQ") (class "Default")
      (node (ref "LED1") (pin "2") (pinfunction "K_2") (pintype "passive"))
      (node (ref "U14") (pin "4") (pintype "passive"))
      (node (ref "U8") (pin "27") (pinfunction "PC1/ETH_MDC/ADC123_IN11_27") (pintype "passive"))
    )
    (net (code "60") (name "/STM32_PC2_LCD_BL") (class "Default")
      (node (ref "LCD") (pin "23") (pinfunction "BL_23") (pintype "passive"))
      (node (ref "U8") (pin "28") (pinfunction "PC2/SPI2_MISO/OTG_HS_ULPI_DIR/ETH_MII_TXD2/I2S2ext_SD/ADC123_IN12_28") (pintype "passive"))
    )
    (net (code "61") (name "/STM32_PC3_LED_PWR") (class "Default")
      (node (ref "R50") (pin "1") (pinfunction "1_1") (pintype "passive"))
      (node (ref "U8") (pin "29") (pinfunction "PC3/SPI2_MOSI/OTG_HS_ULPI_NXT/ETH_MII_TX_CLK/I2S2_SD/ADC123_IN13_29") (pintype "passive"))
    )
    (net (code "62") (name "/STM32_PC4_LED") (class "Default")
      (node (ref "LED2") (pin "2") (pinfunction "K_2") (pintype "passive"))
      (node (ref "U8") (pin "44") (pinfunction "PC4/ETH_MII_RXD0/ETH_RMII_RXD0/ADC12_IN14_44") (pintype "passive"))
    )
    (net (code "63") (name "/STM32_PC5_GM") (class "Default")
      (node (ref "JP2") (pin "1") (pinfunction "1_1") (pintype "passive"))
      (node (ref "R47") (pin "2") (pinfunction "2_2") (pintype "passive"))
      (node (ref "U8") (pin "45") (pinfunction "PC5/ETH_MII_RXD1/ETH_RMII_RXD1/ADC12_IN15_45") (pintype "passive"))
    )
    (net (code "64") (name "/STM32_PC6_DCMI_D0") (class "Default")
      (node (ref "OV2640") (pin "8") (pinfunction "8_8") (pintype "passive"))
      (node (ref "U8") (pin "96") (pinfunction "PC6/TIM3_CH1/TIM8_CH1/U6_TX/SDIO_D6/DCMI_D0/I2S2_MCK_96") (pintype "passive"))
    )
    (net (code "65") (name "/STM32_PC7_DCMI_D1") (class "Default")
      (node (ref "OV2640") (pin "9") (pinfunction "9_9") (pintype "passive"))
      (node (ref "U8") (pin "97") (pinfunction "PC7/TIM3_CH2/TIM8_CH2/U6_RX/SDIO_D7/DCMI_D1/I2S3_MCK_97") (pintype "passive"))
    )
    (net (code "66") (name "/STM32_PC8_DCMI_D2") (class "Default")
      (node (ref "OV2640") (pin "10") (pinfunction "10_10") (pintype "passive"))
      (node (ref "U8") (pin "98") (pinfunction "PC8/TIM3_CH3/TIM8_CH3/U6_CK/SDIO_D0/DCMI_D2_98") (pintype "passive"))
    )
    (net (code "67") (name "/STM32_PC9_DCMI_D3") (class "Default")
      (node (ref "OV2640") (pin "11") (pinfunction "11_11") (pintype "passive"))
      (node (ref "U8") (pin "99") (pinfunction "PC9/TIM3_CH4/TIM8_CH4/I2C3_SDA/SDIO_D1/DCMI_D3/MCO2/I2S_CKIN_99") (pintype "passive"))
    )
    (net (code "68") (name "/STM32_PC11_DCMI_D4") (class "Default")
      (node (ref "OV2640") (pin "12") (pinfunction "12_12") (pintype "passive"))
      (node (ref "U8") (pin "112") (pinfunction "PC11/SPI3_MISO/U3_RX/U4_RX/SDIO_D3/DCMI_D4/I2S3ext_SD_112") (pintype "passive"))
    )
    (net (code "69") (name "/STM32_PC13_LCD_CS") (class "Default")
      (node (ref "LCD") (pin "33") (pinfunction "T_CS_33") (pintype "passive"))
      (node (ref "U8") (pin "7") (pinfunction "PC13/RTC_AF1_7") (pintype "passive"))
    )
    (net (code "70") (name "/STM32_PC13_UART5_TXD") (class "Default")
      (node (ref "U8") (pin "113") (pinfunction "PC12/SPI3_MOSI/U3_CK/U5_TX/SDIO_CK/DCMI_D9/I2S3_SD_113") (pintype "passive"))
    )
    (net (code "71") (name "/STM32_PC14_OSC_IN") (class "Default")
      (node (ref "U8") (pin "8") (pinfunction "PC14-OSC32_IN_8") (pintype "passive"))
    )
    (net (code "72") (name "/STM32_PC15_OSC_OUT") (class "Default")
      (node (ref "U8") (pin "9") (pinfunction "PC15-OSC32_OUT_9") (pintype "passive"))
    )
    (net (code "73") (name "/STM32_PD0_FSMC_D2") (class "Default")
      (node (ref "LCD") (pin "8") (pinfunction "DB3_8") (pintype "passive"))
      (node (ref "U10") (pin "9") (pinfunction "I/O_2_9") (pintype "passive"))
      (node (ref "U8") (pin "114") (pinfunction "PD0/FSMC_D2/CAN1_RX_114") (pintype "passive"))
    )
    (net (code "74") (name "/STM32_PD1_FSMC_D3") (class "Default")
      (node (ref "LCD") (pin "9") (pinfunction "DB4_9") (pintype "passive"))
      (node (ref "U10") (pin "10") (pinfunction "I/O_3_10") (pintype "passive"))
      (node (ref "U8") (pin "115") (pinfunction "PD1/FSMC_D3/CAN1_TX_115") (pintype "passive"))
    )
    (net (code "75") (name "/STM32_PD2_UART5_RXD") (class "Default")
      (node (ref "U8") (pin "116") (pinfunction "PD2/TIM3_ETR/U5_RX/SDIO_CMD/DCMI_D11_116") (pintype "passive"))
    )
    (net (code "76") (name "/STM32_PD3_DHT11") (class "Default")
      (node (ref "DHT11") (pin "2") (pinfunction "DQ_2") (pintype "passive"))
      (node (ref "R83") (pin "2") (pinfunction "2_2") (pintype "passive"))
      (node (ref "U8") (pin "117") (pinfunction "PD3/FSMC_CLK/U2_CTS_117") (pintype "passive"))
    )
    (net (code "77") (name "/STM32_PD4_FSMC_NOE") (class "Default")
      (node (ref "LCD") (pin "4") (pinfunction "RD_4") (pintype "passive"))
      (node (ref "U10") (pin "41") (pinfunction "~{OE}_41") (pintype "passive"))
      (node (ref "U8") (pin "118") (pinfunction "PD4/FSMC_NOE/U2_RTS_118") (pintype "passive"))
    )
    (net (code "78") (name "/STM32_PD5_FSMC_NWE") (class "Default")
      (node (ref "LCD") (pin "3") (pinfunction "WR/CLK_3") (pintype "passive"))
      (node (ref "U10") (pin "17") (pinfunction "~{WE}_17") (pintype "passive"))
      (node (ref "U8") (pin "119") (pinfunction "PD5/FSMC_NWE/U2_TX_119") (pintype "passive"))
    )
    (net (code "79") (name "/STM32_PD6_DCMI_SCL") (class "Default")
      (node (ref "OV2640") (pin "4") (pinfunction "4_4") (pintype "passive"))
      (node (ref "U8") (pin "122") (pinfunction "PD6/FSMC_NWAIT/U2_RX_122") (pintype "passive"))
    )
    (net (code "80") (name "/STM32_PD7_DCMI_SDA") (class "Default")
      (node (ref "OV2640") (pin "6") (pinfunction "6_6") (pintype "passive"))
      (node (ref "U8") (pin "123") (pinfunction "PD7/FSMC_NE1/FSMC_NCE2/U2_CK_123") (pintype "passive"))
    )
    (net (code "81") (name "/STM32_PD8_FSMC_D13") (class "Default")
      (node (ref "LCD") (pin "19") (pinfunction "DB15_19") (pintype "passive"))
      (node (ref "U10") (pin "36") (pinfunction "I/O_13_36") (pintype "passive"))
      (node (ref "U8") (pin "77") (pinfunction "PD8/FSMC_D13/U3_TX_77") (pintype "passive"))
    )
    (net (code "82") (name "/STM32_PD9_FSMC_D14") (class "Default")
      (node (ref "LCD") (pin "20") (pinfunction "DB16_20") (pintype "passive"))
      (node (ref "U10") (pin "37") (pinfunction "I/O_14_37") (pintype "passive"))
      (node (ref "U8") (pin "78") (pinfunction "PD9/FSMC_D14/U3_RX_78") (pintype "passive"))
    )
    (net (code "83") (name "/STM32_PD10_FSMC_D15") (class "Default")
      (node (ref "LCD") (pin "21") (pinfunction "DB17_21") (pintype "passive"))
      (node (ref "U10") (pin "38") (pinfunction "I/O_15_38") (pintype "passive"))
      (node (ref "U8") (pin "79") (pinfunction "PD10/FSMC_D15/U3_CK_79") (pintype "passive"))
    )
    (net (code "84") (name "/STM32_PD11_FSMC_A16") (class "Default")
      (node (ref "U10") (pin "42") (pinfunction "A7_42") (pintype "passive"))
      (node (ref "U8") (pin "80") (pinfunction "PD11/FSMC_A16/FSMC_CLE/U3_CTS_80") (pintype "passive"))
    )
    (net (code "85") (name "/STM32_PD12_FSMC_A17") (class "Default")
      (node (ref "U10") (pin "43") (pinfunction "A6_43") (pintype "passive"))
      (node (ref "U8") (pin "81") (pinfunction "PD12/FSMC_A17/FSMC_ALE/TIM4_CH1/U3_RTS_81") (pintype "passive"))
    )
    (net (code "86") (name "/STM32_PD13_FSMC_A18") (class "Default")
      (node (ref "U10") (pin "44") (pinfunction "A5_44") (pintype "passive"))
      (node (ref "U8") (pin "82") (pinfunction "PD13/FSMC_A18/TIM4_CH2_82") (pintype "passive"))
    )
    (net (code "87") (name "/STM32_PD14_FSMC_D0") (class "Default")
      (node (ref "LCD") (pin "6") (pinfunction "DB1_6") (pintype "passive"))
      (node (ref "U10") (pin "7") (pinfunction "I/O_0_7") (pintype "passive"))
      (node (ref "U8") (pin "85") (pinfunction "PD14/FSMC_D0/TIM4_CH3_85") (pintype "passive"))
    )
    (net (code "88") (name "/STM32_PD15_FSMC_D1") (class "Default")
      (node (ref "LCD") (pin "7") (pinfunction "DB2_7") (pintype "passive"))
      (node (ref "U10") (pin "8") (pinfunction "I/O_1_8") (pintype "passive"))
      (node (ref "U8") (pin "86") (pinfunction "PD15/FSMC_D1/TIM4_CH4_86") (pintype "passive"))
    )
    (net (code "89") (name "/STM32_PE0_FSMC_NBL0") (class "Default")
      (node (ref "U10") (pin "39") (pinfunction "~{LB}_39") (pintype "passive"))
      (node (ref "U8") (pin "141") (pinfunction "PE0/TIM4_ETR/FSMC_NBL0/DCMI_D2_141") (pintype "passive"))
    )
    (net (code "90") (name "/STM32_PE1_FSMC_NBL1") (class "Default")
      (node (ref "U10") (pin "40") (pinfunction "~{UB}_40") (pintype "passive"))
      (node (ref "U8") (pin "142") (pinfunction "PE1/FSMC_NBL1/DCMI_D3_142") (pintype "passive"))
    )
    (net (code "91") (name "/STM32_PE2_EC20_PWR") (class "Default")
      (node (ref "R2") (pin "2") (pinfunction "2_2") (pintype "passive"))
      (node (ref "U8") (pin "1") (pinfunction "PE2/TRACECLK/FSMC_A23/ETH_MII_TXD3_1") (pintype "passive"))
    )
    (net (code "92") (name "/STM32_PE3_EC20_RST") (class "Default")
      (node (ref "R16") (pin "2") (pinfunction "2_2") (pintype "passive"))
      (node (ref "U8") (pin "2") (pinfunction "PE3/TRACED0/FSMC_A19_2") (pintype "passive"))
    )
    (net (code "93") (name "/STM32_PE4_CTRL_485") (class "Default")
      (node (ref "U11") (pin "2") (pinfunction "RE_2") (pintype "passive"))
      (node (ref "U11") (pin "3") (pinfunction "DE_3") (pintype "passive"))
      (node (ref "U8") (pin "3") (pinfunction "PE4/TRACED1/FSMC_A20/DCMI_D4_3") (pintype "passive"))
    )
    (net (code "94") (name "/STM32_PE5_DCMI_D6") (class "Default")
      (node (ref "OV2640") (pin "14") (pinfunction "14_14") (pintype "passive"))
      (node (ref "U8") (pin "4") (pinfunction "PE5/TRACED2/FSMC_A21/TIM9_CH1/DCMI_D6_4") (pintype "passive"))
    )
    (net (code "95") (name "/STM32_PE6_DCMI_D7") (class "Default")
      (node (ref "OV2640") (pin "15") (pinfunction "15_15") (pintype "passive"))
      (node (ref "U8") (pin "5") (pinfunction "PE6/TRACED3/FSMC_A22/TIM9_CH2/DCMI_D7_5") (pintype "passive"))
    )
    (net (code "96") (name "/STM32_PE7_FSMC_D4") (class "Default")
      (node (ref "LCD") (pin "10") (pinfunction "DB5_10") (pintype "passive"))
      (node (ref "U10") (pin "13") (pinfunction "I/O_4_13") (pintype "passive"))
      (node (ref "U8") (pin "58") (pinfunction "PE7/FSMC_D4/TIM1_ETR_58") (pintype "passive"))
    )
    (net (code "97") (name "/STM32_PE8_FSMC_D5") (class "Default")
      (node (ref "LCD") (pin "11") (pinfunction "DB6_11") (pintype "passive"))
      (node (ref "U10") (pin "14") (pinfunction "I/O_5_14") (pintype "passive"))
      (node (ref "U8") (pin "59") (pinfunction "PE8/FSMC_D5/TIM1_CH1N_59") (pintype "passive"))
    )
    (net (code "98") (name "/STM32_PE9_FSMC_D6") (class "Default")
      (node (ref "LCD") (pin "12") (pinfunction "DB7_12") (pintype "passive"))
      (node (ref "U10") (pin "15") (pinfunction "I/O_6_15") (pintype "passive"))
      (node (ref "U8") (pin "60") (pinfunction "PE9/FSMC_D6/TIM1_CH1_60") (pintype "passive"))
    )
    (net (code "99") (name "/STM32_PE10_FSMC_D7") (class "Default")
      (node (ref "LCD") (pin "13") (pinfunction "DB8_13") (pintype "passive"))
      (node (ref "U10") (pin "16") (pinfunction "I/O_7_16") (pintype "passive"))
      (node (ref "U8") (pin "63") (pinfunction "PE10/FSMC_D7/TIM1_CH2N_63") (pintype "passive"))
    )
    (net (code "100") (name "/STM32_PE11_FSMC_D8") (class "Default")
      (node (ref "LCD") (pin "14") (pinfunction "DB10_14") (pintype "passive"))
      (node (ref "U10") (pin "29") (pinfunction "I/O_8_29") (pintype "passive"))
      (node (ref "U8") (pin "64") (pinfunction "PE11/FSMC_D8/TIM1_CH2_64") (pintype "passive"))
    )
    (net (code "101") (name "/STM32_PE12_FSMC_D9") (class "Default")
      (node (ref "LCD") (pin "15") (pinfunction "DB11_15") (pintype "passive"))
      (node (ref "U10") (pin "30") (pinfunction "I/O_9_30") (pintype "passive"))
      (node (ref "U8") (pin "65") (pinfunction "PE12/FSMC_D9/TIM1_CH3N_65") (pintype "passive"))
    )
    (net (code "102") (name "/STM32_PE13_FSMC_D10") (class "Default")
      (node (ref "LCD") (pin "16") (pinfunction "DB12_16") (pintype "passive"))
      (node (ref "U10") (pin "31") (pinfunction "I/O_10_31") (pintype "passive"))
      (node (ref "U8") (pin "66") (pinfunction "PE13/FSMC_D10/TIM1_CH3_66") (pintype "passive"))
    )
    (net (code "103") (name "/STM32_PE14_FSMC_D11") (class "Default")
      (node (ref "LCD") (pin "17") (pinfunction "DB13_17") (pintype "passive"))
      (node (ref "U10") (pin "32") (pinfunction "I/O_11_32") (pintype "passive"))
      (node (ref "U8") (pin "67") (pinfunction "PE14/FSMC_D11/TIM1_CH4_67") (pintype "passive"))
    )
    (net (code "104") (name "/STM32_PE15_FSMC_D12") (class "Default")
      (node (ref "LCD") (pin "18") (pinfunction "DB14_18") (pintype "passive"))
      (node (ref "U10") (pin "35") (pinfunction "I/O_12_35") (pintype "passive"))
      (node (ref "U8") (pin "68") (pinfunction "PE15/FSMC_D12/TIM1_BKIN_68") (pintype "passive"))
    )
    (net (code "105") (name "/STM32_PF0_FSMC_A0") (class "Default")
      (node (ref "U10") (pin "5") (pinfunction "A0_5") (pintype "passive"))
      (node (ref "U8") (pin "10") (pinfunction "PF0/FSMC_A0/I2C2_SDA_10") (pintype "passive"))
    )
    (net (code "106") (name "/STM32_PF1_FSMC_A1") (class "Default")
      (node (ref "U10") (pin "4") (pinfunction "A1_4") (pintype "passive"))
      (node (ref "U8") (pin "11") (pinfunction "PF1/FSMC_A1/I2C2_SCL_11") (pintype "passive"))
    )
    (net (code "107") (name "/STM32_PF2_FSMC_A2") (class "Default")
      (node (ref "U10") (pin "3") (pinfunction "A2_3") (pintype "passive"))
      (node (ref "U8") (pin "12") (pinfunction "PF2/FSMC_A2/I2C2_SMBA_12") (pintype "passive"))
    )
    (net (code "108") (name "/STM32_PF3_FSMC_A3") (class "Default")
      (node (ref "U10") (pin "2") (pinfunction "A3_2") (pintype "passive"))
      (node (ref "U8") (pin "13") (pinfunction "PF3/FSMC_A3/ADC3_IN9_13") (pintype "passive"))
    )
    (net (code "109") (name "/STM32_PF4_FSMC_A4") (class "Default")
      (node (ref "U10") (pin "1") (pinfunction "A4_1") (pintype "passive"))
      (node (ref "U8") (pin "14") (pinfunction "PF4/FSMC_A4/ADC3_IN14_14") (pintype "passive"))
    )
    (net (code "110") (name "/STM32_PF5_FSMC_A5") (class "Default")
      (node (ref "U10") (pin "24") (pinfunction "A11_24") (pintype "passive"))
      (node (ref "U8") (pin "15") (pinfunction "PF5/FSMC_A5/ADC3_IN15_15") (pintype "passive"))
    )
    (net (code "111") (name "/STM32_PF11_LCD_MOSI") (class "Default")
      (node (ref "LCD") (pin "30") (pinfunction "MOSI_30") (pintype "passive"))
      (node (ref "U8") (pin "49") (pinfunction "PF11/DCMI_D12_49") (pintype "passive"))
    )
    (net (code "112") (name "/STM32_PF12_FSMC_A6") (class "Default")
      (node (ref "LCD") (pin "2") (pinfunction "RS_2") (pintype "passive"))
      (node (ref "U10") (pin "23") (pinfunction "A17_23") (pintype "passive"))
      (node (ref "U8") (pin "50") (pinfunction "PF12/FSMC_A6_50") (pintype "passive"))
    )
    (net (code "113") (name "/STM32_PF13_FSMC_A7") (class "Default")
      (node (ref "U10") (pin "22") (pinfunction "A12_22") (pintype "passive"))
      (node (ref "U8") (pin "53") (pinfunction "PF13/FSMC_A7_53") (pintype "passive"))
    )
    (net (code "114") (name "/STM32_PF14_FSMC_A8") (class "Default")
      (node (ref "U10") (pin "21") (pinfunction "A13_21") (pintype "passive"))
      (node (ref "U8") (pin "54") (pinfunction "PF14/FSMC_A8_54") (pintype "passive"))
    )
    (net (code "115") (name "/STM32_PF15_FSMC_A9") (class "Default")
      (node (ref "U10") (pin "20") (pinfunction "A14_20") (pintype "passive"))
      (node (ref "U8") (pin "55") (pinfunction "PF15/FSMC_A9_55") (pintype "passive"))
    )
    (net (code "116") (name "/STM32_PG0_FSMC_A10") (class "Default")
      (node (ref "U10") (pin "19") (pinfunction "A15_19") (pintype "passive"))
      (node (ref "U8") (pin "56") (pinfunction "PG0/FSMC_A10_56") (pintype "passive"))
    )
    (net (code "117") (name "/STM32_PG1_FSMC_A11") (class "Default")
      (node (ref "U10") (pin "18") (pinfunction "A16_18") (pintype "passive"))
      (node (ref "U8") (pin "57") (pinfunction "PG1/FSMC_A11_57") (pintype "passive"))
    )
    (net (code "118") (name "/STM32_PG2_FSMC_A12") (class "Default")
      (node (ref "U10") (pin "28") (pinfunction "A18_28") (pintype "passive"))
      (node (ref "U8") (pin "87") (pinfunction "PG2/FSMC_A12_87") (pintype "passive"))
    )
    (net (code "119") (name "/STM32_PG3_FSMC_A13") (class "Default")
      (node (ref "U10") (pin "27") (pinfunction "A8_27") (pintype "passive"))
      (node (ref "U8") (pin "88") (pinfunction "PG3/FSMC_A13_88") (pintype "passive"))
    )
    (net (code "120") (name "/STM32_PG4_FSMC_A14") (class "Default")
      (node (ref "U10") (pin "26") (pinfunction "A9_26") (pintype "passive"))
      (node (ref "U8") (pin "89") (pinfunction "PG4/FSMC_A14_89") (pintype "passive"))
    )
    (net (code "121") (name "/STM32_PG5_FSMC_A15") (class "Default")
      (node (ref "U10") (pin "25") (pinfunction "A10_25") (pintype "passive"))
      (node (ref "U8") (pin "90") (pinfunction "PG5/FSMC_A15_90") (pintype "passive"))
    )
    (net (code "122") (name "/STM32_PG9_DCMI_PWDN") (class "Default")
      (node (ref "OV2640") (pin "18") (pinfunction "18_18") (pintype "passive"))
      (node (ref "U8") (pin "124") (pinfunction "PG9/FSMC_NE2/FSMC_NCE3/U6_RX_124") (pintype "passive"))
    )
    (net (code "123") (name "/STM32_PG10_FSMC_NE3") (class "Default")
      (node (ref "R34") (pin "1") (pinfunction "1_1") (pintype "passive"))
      (node (ref "U10") (pin "6") (pinfunction "~{CE}_6") (pintype "passive"))
      (node (ref "U8") (pin "125") (pinfunction "PG10/FSMC_NCE4_1/FSMC_NE3_125") (pintype "passive"))
    )
    (net (code "124") (name "/STM32_PG12_FSMC_NE4") (class "Default")
      (node (ref "LCD") (pin "1") (pinfunction "LCD_CS_1") (pintype "passive"))
      (node (ref "U8") (pin "127") (pinfunction "PG12/FSMC_NE4/U6_RTS_127") (pintype "passive"))
    )
    (net (code "125") (name "/STM32_PG15_DCMI_RESET") (class "Default")
      (node (ref "OV2640") (pin "7") (pinfunction "7_7") (pintype "passive"))
      (node (ref "U8") (pin "132") (pinfunction "PG15/U6_CTS/DCMI_D13_132") (pintype "passive"))
    )
    (net (code "126") (name "/UART2_CTS") (class "Default")
      (node (ref "R23") (pin "2") (pinfunction "2_2") (pintype "passive"))
      (node (ref "U7") (pin "10") (pinfunction "B4_10") (pintype "passive"))
    )
    (net (code "127") (name "/UART2_RTS") (class "Default")
      (node (ref "R25") (pin "2") (pinfunction "2_2") (pintype "passive"))
      (node (ref "U7") (pin "11") (pinfunction "B3_11") (pintype "passive"))
    )
    (net (code "128") (name "/UART2_RX") (class "Default")
      (node (ref "R26") (pin "2") (pinfunction "2_2") (pintype "passive"))
      (node (ref "U7") (pin "13") (pinfunction "B1_13") (pintype "passive"))
    )
    (net (code "129") (name "/UART2_TX") (class "Default")
      (node (ref "R24") (pin "2") (pinfunction "2_2") (pintype "passive"))
      (node (ref "U7") (pin "12") (pinfunction "B2_12") (pintype "passive"))
    )
    (net (code "130") (name "/USIM_CLK") (class "Default")
      (node (ref "C14") (pin "1") (pinfunction "1_1") (pintype "passive"))
      (node (ref "R12") (pin "2") (pinfunction "2_2") (pintype "passive"))
      (node (ref "U5") (pin "12") (pinfunction "EC20_USIM_CLK/7600CE_USIM_CLK_12") (pintype "passive"))
    )
    (net (code "131") (name "/USIM_DATA") (class "Default")
      (node (ref "R13") (pin "1") (pinfunction "1_1") (pintype "passive"))
      (node (ref "U5") (pin "10") (pinfunction "EC20_USIM_DATA/7600CE_USIM_DATA_10") (pintype "passive"))
    )
    (net (code "132") (name "/USIM_RST") (class "Default")
      (node (ref "C13") (pin "2") (pinfunction "2_2") (pintype "passive"))
      (node (ref "R11") (pin "2") (pinfunction "2_2") (pintype "passive"))
      (node (ref "U5") (pin "14") (pinfunction "EC20_USIM_RST/7600CE_USIM_RST_14") (pintype "passive"))
    )
    (net (code "133") (name "/VDDA") (class "Default")
      (node (ref "C59") (pin "1") (pinfunction "1_1") (pintype "passive"))
      (node (ref "C60") (pin "1") (pinfunction "1_1") (pintype "passive"))
      (node (ref "R70") (pin "2") (pinfunction "2_2") (pintype "passive"))
      (node (ref "R72") (pin "1") (pinfunction "1_1") (pintype "passive"))
      (node (ref "U8") (pin "33") (pinfunction "VDDA_33") (pintype "passive"))
    )
    (net (code "134") (name "GND") (class "Default")
      (node (ref "ADC") (pin "2") (pinfunction "2_2") (pintype "passive"))
      (node (ref "C1") (pin "2") (pinfunction "2_2") (pintype "passive"))
      (node (ref "C10") (pin "2") (pinfunction "2_2") (pintype "passive"))
      (node (ref "C11") (pin "2") (pinfunction "2_2") (pintype "passive"))
      (node (ref "C12") (pin "2") (pinfunction "2_2") (pintype "passive"))
      (node (ref "C120") (pin "1") (pinfunction "1_1") (pintype "passive"))
      (node (ref "C13") (pin "1") (pinfunction "1_1") (pintype "passive"))
      (node (ref "C14") (pin "2") (pinfunction "2_2") (pintype "passive"))
      (node (ref "C15") (pin "2") (pinfunction "2_2") (pintype "passive"))
      (node (ref "C16") (pin "1") (pinfunction "1_1") (pintype "passive"))
      (node (ref "C17") (pin "1") (pinfunction "1_1") (pintype "passive"))
      (node (ref "C18") (pin "1") (pinfunction "1_1") (pintype "passive"))
      (node (ref "C19") (pin "1") (pinfunction "1_1") (pintype "passive"))
      (node (ref "C2") (pin "2") (pinfunction "2_2") (pintype "passive"))
      (node (ref "C20") (pin "1") (pinfunction "1_1") (pintype "passive"))
      (node (ref "C21") (pin "2") (pinfunction "2_2") (pintype "passive"))
      (node (ref "C22") (pin "2") (pinfunction "2_2") (pintype "passive"))
      (node (ref "C23") (pin "1") (pinfunction "1_1") (pintype "passive"))
      (node (ref "C24") (pin "1") (pinfunction "1_1") (pintype "passive"))
      (node (ref "C25") (pin "1") (pinfunction "1_1") (pintype "passive"))
      (node (ref "C26") (pin "1") (pinfunction "1_1") (pintype "passive"))
      (node (ref "C27") (pin "1") (pinfunction "1_1") (pintype "passive"))
      (node (ref "C28") (pin "1") (pinfunction "1_1") (pintype "passive"))
      (node (ref "C29") (pin "1") (pinfunction "1_1") (pintype "passive"))
      (node (ref "C3") (pin "1") (pinfunction "1_1") (pintype "passive"))
      (node (ref "C30") (pin "1") (pinfunction "1_1") (pintype "passive"))
      (node (ref "C31") (pin "1") (pinfunction "1_1") (pintype "passive"))
      (node (ref "C32") (pin "1") (pinfunction "1_1") (pintype "passive"))
      (node (ref "C33") (pin "1") (pinfunction "1_1") (pintype "passive"))
      (node (ref "C34") (pin "1") (pinfunction "1_1") (pintype "passive"))
      (node (ref "C35") (pin "1") (pinfunction "1_1") (pintype "passive"))
      (node (ref "C36") (pin "2") (pinfunction "2_2") (pintype "passive"))
      (node (ref "C37") (pin "2") (pinfunction "2_2") (pintype "passive"))
      (node (ref "C4") (pin "2") (pinfunction "2_2") (pintype "passive"))
      (node (ref "C40") (pin "2") (pinfunction "2_2") (pintype "passive"))
      (node (ref "C41") (pin "2") (pinfunction "2_2") (pintype "passive"))
      (node (ref "C42") (pin "2") (pinfunction "2_2") (pintype "passive"))
      (node (ref "C43") (pin "1") (pinfunction "1_1") (pintype "passive"))
      (node (ref "C44") (pin "1") (pinfunction "1_1") (pintype "passive"))
      (node (ref "C45") (pin "2") (pinfunction "2_2") (pintype "passive"))
      (node (ref "C47") (pin "2") (pinfunction "2_2") (pintype "passive"))
      (node (ref "C48") (pin "2") (pinfunction "2_2") (pintype "passive"))
      (node (ref "C49") (pin "2") (pinfunction "2_2") (pintype "passive"))
      (node (ref "C5") (pin "1") (pinfunction "1_1") (pintype "passive"))
      (node (ref "C50") (pin "1") (pinfunction "1_1") (pintype "passive"))
      (node (ref "C51") (pin "1") (pinfunction "1_1") (pintype "passive"))
      (node (ref "C52") (pin "1") (pinfunction "1_1") (pintype "passive"))
      (node (ref "C54") (pin "1") (pinfunction "1_1") (pintype "passive"))
      (node (ref "C55") (pin "1") (pinfunction "1_1") (pintype "passive"))
      (node (ref "C56") (pin "2") (pinfunction "2_2") (pintype "passive"))
      (node (ref "C57") (pin "2") (pinfunction "2_2") (pintype "passive"))
      (node (ref "C59") (pin "2") (pinfunction "2_2") (pintype "passive"))
      (node (ref "C60") (pin "2") (pinfunction "2_2") (pintype "passive"))
      (node (ref "C61") (pin "1") (pinfunction "1_1") (pintype "passive"))
      (node (ref "C77") (pin "1") (pinfunction "1_1") (pintype "passive"))
      (node (ref "C9") (pin "1") (pinfunction "1_1") (pintype "passive"))
      (node (ref "D1") (pin "1") (pinfunction "1_1") (pintype "passive"))
      (node (ref "D4") (pin "1") (pinfunction "A_1") (pintype "passive"))
      (node (ref "DHT11") (pin "3") (pinfunction "NC_3") (pintype "passive"))
      (node (ref "DHT11") (pin "4") (pinfunction "GND_4") (pintype "passive"))
      (node (ref "JP1") (pin "2") (pinfunction "2_2") (pintype "passive"))
      (node (ref "JP2") (pin "2") (pinfunction "2_2") (pintype "passive"))
      (node (ref "JTAG") (pin "10") (pinfunction "GND_10") (pintype "passive"))
      (node (ref "JTAG") (pin "12") (pinfunction "GND_12") (pintype "passive"))
      (node (ref "JTAG") (pin "14") (pinfunction "GND_14") (pintype "passive"))
      (node (ref "JTAG") (pin "16") (pinfunction "GND_16") (pintype "passive"))
      (node (ref "JTAG") (pin "18") (pinfunction "GND_18") (pintype "passive"))
      (node (ref "JTAG") (pin "20") (pinfunction "GND_20") (pintype "passive"))
      (node (ref "JTAG") (pin "4") (pinfunction "GND_4") (pintype "passive"))
      (node (ref "JTAG") (pin "6") (pinfunction "GND_6") (pintype "passive"))
      (node (ref "JTAG") (pin "8") (pinfunction "GND_8") (pintype "passive"))
      (node (ref "LCD") (pin "22") (pinfunction "GND_22") (pintype "passive"))
      (node (ref "LCD") (pin "26") (pinfunction "GND_26") (pintype "passive"))
      (node (ref "LCD") (pin "27") (pinfunction "GND_27") (pintype "passive"))
      (node (ref "LED") (pin "2") (pinfunction "2_2") (pintype "passive"))
      (node (ref "OV2640") (pin "2") (pinfunction "2_2") (pintype "passive"))
      (node (ref "POW") (pin "2") (pinfunction "2_2") (pintype "passive"))
      (node (ref "Q1") (pin "2") (pinfunction "E_2") (pintype "passive"))
      (node (ref "Q2") (pin "2") (pinfunction "E_2") (pintype "passive"))
      (node (ref "Q6") (pin "2") (pinfunction "S_2") (pintype "passive"))
      (node (ref "R17") (pin "1") (pinfunction "1_1") (pintype "passive"))
      (node (ref "R27") (pin "1") (pinfunction "1_1") (pintype "passive"))
      (node (ref "R3") (pin "2") (pinfunction "2_2") (pintype "passive"))
      (node (ref "R33") (pin "1") (pinfunction "1_1") (pintype "passive"))
      (node (ref "R36") (pin "2") (pinfunction "2_2") (pintype "passive"))
      (node (ref "R38") (pin "1") (pinfunction "1_1") (pintype "passive"))
      (node (ref "R40") (pin "1") (pinfunction "1_1") (pintype "passive"))
      (node (ref "R5") (pin "2") (pinfunction "2_2") (pintype "passive"))
      (node (ref "R51") (pin "2") (pinfunction "2_2") (pintype "passive"))
      (node (ref "R6") (pin "2") (pinfunction "2_2") (pintype "passive"))
      (node (ref "R7") (pin "2") (pinfunction "2_2") (pintype "passive"))
      (node (ref "R73") (pin "1") (pinfunction "1_1") (pintype "passive"))
      (node (ref "R8") (pin "1") (pinfunction "1_1") (pintype "passive"))
      (node (ref "R82") (pin "2") (pinfunction "2_2") (pintype "passive"))
      (node (ref "SIM") (pin "4") (pinfunction "GND_4") (pintype "passive"))
      (node (ref "SYS_REST") (pin "1") (pinfunction "1_1") (pintype "passive"))
      (node (ref "TVS1") (pin "1") (pinfunction "A_1") (pintype "passive"))
      (node (ref "TVS2") (pin "1") (pinfunction "A_1") (pintype "passive"))
      (node (ref "TVS3") (pin "1") (pinfunction "A_1") (pintype "passive"))
      (node (ref "U1") (pin "3") (pinfunction "Ground_3") (pintype "passive"))
      (node (ref "U1") (pin "5") (pinfunction "ON/OFF_5") (pintype "passive"))
      (node (ref "U1") (pin "6") (pinfunction "GND_6") (pintype "passive"))
      (node (ref "U10") (pin "12") (pinfunction "GND_12") (pintype "passive"))
      (node (ref "U10") (pin "34") (pinfunction "GND_34") (pintype "passive"))
      (node (ref "U11") (pin "5") (pinfunction "GND_5") (pintype "passive"))
      (node (ref "U12") (pin "2") (pinfunction "GND_2") (pintype "passive"))
      (node (ref "U13") (pin "1") (pinfunction "GND_1") (pintype "passive"))
      (node (ref "U14") (pin "3") (pintype "passive"))
      (node (ref "U15") (pin "2") (pinfunction "GND_2") (pintype "power_in"))
      (node (ref "U15") (pin "8") (pinfunction "RS_8") (pintype "input"))
      (node (ref "U2") (pin "3") (pinfunction "GND_3") (pintype "passive"))
      (node (ref "U3") (pin "1") (pinfunction "GND_1") (pintype "passive"))
      (node (ref "U4") (pin "4") (pinfunction "VEE/GND_4") (pintype "passive"))
      (node (ref "U5") (pin "15") (pinfunction "GND_15") (pintype "passive"))
      (node (ref "U5") (pin "18") (pinfunction "GND_18") (pintype "passive"))
      (node (ref "U5") (pin "21") (pinfunction "GND_21") (pintype "passive"))
      (node (ref "U5") (pin "26") (pinfunction "GND_26") (pintype "passive"))
      (node (ref "U5") (pin "27") (pinfunction "GND_27") (pintype "passive"))
      (node (ref "U5") (pin "29") (pinfunction "GND_29") (pintype "passive"))
      (node (ref "U5") (pin "34") (pinfunction "GND_34") (pintype "passive"))
      (node (ref "U5") (pin "35") (pinfunction "GND_35") (pintype "passive"))
      (node (ref "U5") (pin "37") (pinfunction "GND_37") (pintype "passive"))
      (node (ref "U5") (pin "4") (pinfunction "GND_4") (pintype "passive"))
      (node (ref "U5") (pin "40") (pinfunction "GND_40") (pintype "passive"))
      (node (ref "U5") (pin "43") (pinfunction "GND_43") (pintype "passive"))
      (node (ref "U5") (pin "50") (pinfunction "GND_50") (pintype "passive"))
      (node (ref "U5") (pin "9") (pinfunction "GND_9") (pintype "passive"))
      (node (ref "U6") (pin "2") (pintype "passive"))
      (node (ref "U7") (pin "7") (pinfunction "GND_7") (pintype "passive"))
      (node (ref "U8") (pin "107") (pinfunction "VSS_107") (pintype "passive"))
      (node (ref "U8") (pin "120") (pinfunction "VSS_120") (pintype "passive"))
      (node (ref "U8") (pin "130") (pinfunction "VSS_130") (pintype "passive"))
      (node (ref "U8") (pin "16") (pinfunction "VSS_16") (pintype "passive"))
      (node (ref "U8") (pin "31") (pinfunction "VSSA_31") (pintype "passive"))
      (node (ref "U8") (pin "38") (pinfunction "VSS_38") (pintype "passive"))
      (node (ref "U8") (pin "51") (pinfunction "VSS_51") (pintype "passive"))
      (node (ref "U8") (pin "61") (pinfunction "VSS_61") (pintype "passive"))
      (node (ref "U8") (pin "83") (pinfunction "VSS_83") (pintype "passive"))
      (node (ref "U8") (pin "94") (pinfunction "VSS_94") (pintype "passive"))
      (node (ref "U9") (pin "4") (pinfunction "GND_4") (pintype "passive"))
      (node (ref "USB") (pin "5") (pinfunction "GND_5") (pintype "passive"))
      (node (ref "USB") (pin "6") (pinfunction "GND_6") (pintype "passive"))
      (node (ref "USB") (pin "7") (pinfunction "GND_7") (pintype "passive"))
      (node (ref "USB") (pin "8") (pinfunction "GND_8") (pintype "passive"))
      (node (ref "USB") (pin "9") (pinfunction "GND_9") (pintype "passive"))
      (node (ref "USB2") (pin "5") (pinfunction "GND_5") (pintype "passive"))
      (node (ref "USB2") (pin "6") (pinfunction "GND_6") (pintype "passive"))
      (node (ref "USB2") (pin "7") (pinfunction "GND_7") (pintype "passive"))
      (node (ref "USB2") (pin "8") (pinfunction "GND_8") (pintype "passive"))
      (node (ref "USB2") (pin "9") (pinfunction "GND_9") (pintype "passive"))
    )
    (net (code "135") (name "Net-(ADC-Pad1)") (class "Default")
      (node (ref "ADC") (pin "1") (pinfunction "1_1") (pintype "passive"))
      (node (ref "C9") (pin "2") (pinfunction "2_2") (pintype "passive"))
      (node (ref "R38") (pin "2") (pinfunction "2_2") (pintype "passive"))
      (node (ref "R39") (pin "1") (pinfunction "1_1") (pintype "passive"))
    )
    (net (code "136") (name "Net-(BOOT0-Pad1)") (class "Default")
      (node (ref "BOOT0") (pin "1") (pinfunction "1_1") (pintype "passive"))
      (node (ref "R32") (pin "1") (pinfunction "1_1") (pintype "passive"))
    )
    (net (code "137") (name "Net-(BOOT0-Pad3)") (class "Default")
      (node (ref "BOOT0") (pin "3") (pinfunction "3_3") (pintype "passive"))
      (node (ref "R33") (pin "2") (pinfunction "2_2") (pintype "passive"))
    )
    (net (code "138") (name "Net-(JTAG-RTCK)") (class "Default")
      (node (ref "JTAG") (pin "11") (pinfunction "RTCK_11") (pintype "passive"))
      (node (ref "R73") (pin "2") (pinfunction "2_2") (pintype "passive"))
    )
    (net (code "139") (name "Net-(LED1-A)") (class "Default")
      (node (ref "LED1") (pin "1") (pinfunction "A_1") (pintype "passive"))
      (node (ref "R55") (pin "1") (pinfunction "1_1") (pintype "passive"))
    )
    (net (code "140") (name "Net-(LED2-A)") (class "Default")
      (node (ref "LED2") (pin "1") (pinfunction "A_1") (pintype "passive"))
      (node (ref "R19") (pin "2") (pinfunction "2_2") (pintype "passive"))
    )
    (net (code "141") (name "Net-(LED3-A)") (class "Default")
      (node (ref "LED3") (pin "1") (pinfunction "A_1") (pintype "passive"))
      (node (ref "R62") (pin "2") (pinfunction "2_2") (pintype "passive"))
    )
    (net (code "142") (name "Net-(LED4-A)") (class "Default")
      (node (ref "LED4") (pin "1") (pinfunction "A_1") (pintype "passive"))
      (node (ref "R63") (pin "2") (pinfunction "2_2") (pintype "passive"))
    )
    (net (code "143") (name "Net-(NET-Pad1)") (class "Default")
      (node (ref "NET") (pin "1") (pinfunction "1_1") (pintype "passive"))
      (node (ref "R22") (pin "1") (pinfunction "1_1") (pintype "passive"))
    )
    (net (code "144") (name "Net-(POW-Pad1)") (class "Default")
      (node (ref "POW") (pin "1") (pinfunction "1_1") (pintype "passive"))
      (node (ref "R18") (pin "1") (pinfunction "1_1") (pintype "passive"))
    )
    (net (code "145") (name "Net-(Q1-B)") (class "Default")
      (node (ref "Q1") (pin "1") (pinfunction "B_1") (pintype "passive"))
      (node (ref "R2") (pin "1") (pinfunction "1_1") (pintype "passive"))
      (node (ref "R3") (pin "1") (pinfunction "1_1") (pintype "passive"))
    )
    (net (code "146") (name "Net-(Q1-C)") (class "Default")
      (node (ref "Q1") (pin "3") (pinfunction "C_3") (pintype "passive"))
      (node (ref "R1") (pin "2") (pinfunction "2_2") (pintype "passive"))
      (node (ref "U2") (pin "1") (pinfunction "EN_1") (pintype "passive"))
    )
    (net (code "147") (name "Net-(Q2-B)") (class "Default")
      (node (ref "Q2") (pin "1") (pinfunction "B_1") (pintype "passive"))
      (node (ref "R16") (pin "1") (pinfunction "1_1") (pintype "passive"))
      (node (ref "R17") (pin "2") (pinfunction "2_2") (pintype "passive"))
    )
    (net (code "148") (name "Net-(Q3-B)") (class "Default")
      (node (ref "Q3") (pin "1") (pinfunction "B_1") (pintype "passive"))
      (node (ref "R43") (pin "1") (pinfunction "1_1") (pintype "passive"))
    )
    (net (code "149") (name "Net-(Q3-C)") (class "Default")
      (node (ref "D3") (pin "2") (pinfunction "2_2") (pintype "passive"))
      (node (ref "Q3") (pin "3") (pinfunction "C_3") (pintype "passive"))
      (node (ref "R44") (pin "2") (pinfunction "2_2") (pintype "passive"))
    )
    (net (code "150") (name "Net-(Q3-E)") (class "Default")
      (node (ref "Q3") (pin "2") (pinfunction "E_2") (pintype "passive"))
      (node (ref "R45") (pin "2") (pinfunction "2_2") (pintype "passive"))
      (node (ref "U13") (pin "14") (pinfunction "RTS_14") (pintype "passive"))
    )
    (net (code "151") (name "Net-(Q4-B)") (class "Default")
      (node (ref "Q4") (pin "1") (pinfunction "B_1") (pintype "passive"))
      (node (ref "R45") (pin "1") (pinfunction "1_1") (pintype "passive"))
    )
    (net (code "152") (name "Net-(Q4-E)") (class "Default")
      (node (ref "Q4") (pin "2") (pinfunction "E_2") (pintype "passive"))
      (node (ref "R46") (pin "2") (pinfunction "2_2") (pintype "passive"))
    )
    (net (code "153") (name "Net-(Q6-D)") (class "Default")
      (node (ref "Q6") (pin "3") (pinfunction "D_3") (pintype "passive"))
      (node (ref "Q7") (pin "1") (pinfunction "G_1") (pintype "passive"))
      (node (ref "R52") (pin "1") (pinfunction "1_1") (pintype "passive"))
    )
    (net (code "154") (name "Net-(Q6-G)") (class "Default")
      (node (ref "Q6") (pin "1") (pinfunction "G_1") (pintype "passive"))
      (node (ref "R50") (pin "2") (pinfunction "2_2") (pintype "passive"))
      (node (ref "R51") (pin "1") (pinfunction "1_1") (pintype "passive"))
    )
    (net (code "155") (name "Net-(R53-Pad1)") (class "Default")
      (node (ref "R53") (pin "1") (pinfunction "1_1") (pintype "passive"))
      (node (ref "R54") (pin "1") (pinfunction "1_1") (pintype "passive"))
      (node (ref "U14") (pin "1") (pintype "passive"))
    )
    (net (code "156") (name "Net-(R74-Pad1)") (class "Default")
      (node (ref "R74") (pin "1") (pinfunction "1_1") (pintype "passive"))
      (node (ref "SIM") (pin "8") (pinfunction "VCC_8") (pintype "passive"))
    )
    (net (code "157") (name "Net-(SIM-CCIN)") (class "Default")
      (node (ref "R74") (pin "2") (pinfunction "2_2") (pintype "passive"))
      (node (ref "SIM") (pin "7") (pinfunction "CCIN_7") (pintype "passive"))
    )
    (net (code "158") (name "Net-(SIM-CLK)") (class "Default")
      (node (ref "R12") (pin "1") (pinfunction "1_1") (pintype "passive"))
      (node (ref "SIM") (pin "3") (pinfunction "CLK_3") (pintype "passive"))
      (node (ref "U6") (pin "3") (pintype "passive"))
    )
    (net (code "159") (name "Net-(SIM-IO)") (class "Default")
      (node (ref "C16") (pin "2") (pinfunction "2_2") (pintype "passive"))
      (node (ref "R13") (pin "2") (pinfunction "2_2") (pintype "passive"))
      (node (ref "R14") (pin "1") (pinfunction "1_1") (pintype "passive"))
      (node (ref "SIM") (pin "6") (pinfunction "IO_6") (pintype "passive"))
      (node (ref "U6") (pin "6") (pintype "passive"))
    )
    (net (code "160") (name "Net-(SIM-RST)") (class "Default")
      (node (ref "R11") (pin "1") (pinfunction "1_1") (pintype "passive"))
      (node (ref "SIM") (pin "2") (pinfunction "RST_2") (pintype "passive"))
      (node (ref "U6") (pin "4") (pintype "passive"))
    )
    (net (code "161") (name "Net-(U1-Output)") (class "Default")
      (node (ref "D1") (pin "2") (pinfunction "2_2") (pintype "passive"))
      (node (ref "L1") (pin "1") (pinfunction "1_1") (pintype "passive"))
      (node (ref "U1") (pin "2") (pinfunction "Output_2") (pintype "passive"))
    )
    (net (code "162") (name "Net-(U2-ADJ)") (class "Default")
      (node (ref "R4") (pin "2") (pinfunction "2_2") (pintype "passive"))
      (node (ref "R5") (pin "1") (pinfunction "1_1") (pintype "passive"))
      (node (ref "U2") (pin "5") (pinfunction "ADJ_5") (pintype "passive"))
    )
    (net (code "163") (name "Net-(U4-Inputs_A+)") (class "Default")
      (node (ref "R39") (pin "2") (pinfunction "2_2") (pintype "passive"))
      (node (ref "U4") (pin "3") (pinfunction "Inputs_A+_3") (pintype "passive"))
    )
    (net (code "164") (name "Net-(U4-Inputs_A-)") (class "Default")
      (node (ref "R40") (pin "2") (pinfunction "2_2") (pintype "passive"))
      (node (ref "R69") (pin "2") (pinfunction "2_2") (pintype "passive"))
      (node (ref "U4") (pin "2") (pinfunction "Inputs_A-_2") (pintype "passive"))
    )
    (net (code "165") (name "Net-(U4-Output_A)") (class "Default")
      (node (ref "R68") (pin "2") (pinfunction "2_2") (pintype "passive"))
      (node (ref "U4") (pin "1") (pinfunction "Output_A_1") (pintype "passive"))
    )
    (net (code "166") (name "Net-(U8-PDR_ON)") (class "Default")
      (node (ref "R71") (pin "2") (pinfunction "2_2") (pintype "passive"))
      (node (ref "U8") (pin "143") (pinfunction "PDR_ON_143") (pintype "passive"))
    )
    (net (code "167") (name "Net-(U8-Vcap_1)") (class "Default")
      (node (ref "C56") (pin "1") (pinfunction "1_1") (pintype "passive"))
      (node (ref "U8") (pin "71") (pinfunction "Vcap_1_71") (pintype "passive"))
    )
    (net (code "168") (name "Net-(U8-Vcap_2)") (class "Default")
      (node (ref "C57") (pin "1") (pinfunction "1_1") (pintype "passive"))
      (node (ref "U8") (pin "106") (pinfunction "Vcap_2_106") (pintype "passive"))
    )
    (net (code "169") (name "Net-(U8-Vref+)") (class "Default")
      (node (ref "R72") (pin "2") (pinfunction "2_2") (pintype "passive"))
      (node (ref "U8") (pin "32") (pinfunction "Vref+_32") (pintype "passive"))
    )
    (net (code "170") (name "Net-(U9-WP#)") (class "Default")
      (node (ref "R60") (pin "2") (pinfunction "2_2") (pintype "passive"))
      (node (ref "U9") (pin "3") (pinfunction "WP#_3") (pintype "passive"))
    )
    (net (code "171") (name "Net-(U11-DI)") (class "Default")
      (node (ref "R66") (pin "1") (pinfunction "1_1") (pintype "passive"))
      (node (ref "U11") (pin "4") (pinfunction "DI_4") (pintype "passive"))
    )
    (net (code "172") (name "Net-(U11-RO)") (class "Default")
      (node (ref "R67") (pin "1") (pinfunction "1_1") (pintype "passive"))
      (node (ref "U11") (pin "1") (pinfunction "RO_1") (pintype "passive"))
    )
    (net (code "173") (name "Net-(U12-BP)") (class "Default")
      (node (ref "C11") (pin "1") (pinfunction "1_1") (pintype "passive"))
      (node (ref "U12") (pin "4") (pinfunction "BP_4") (pintype "passive"))
    )
    (net (code "174") (name "Net-(U13-DTR)") (class "Default")
      (node (ref "R43") (pin "2") (pinfunction "2_2") (pintype "passive"))
      (node (ref "U13") (pin "13") (pinfunction "DTR_13") (pintype "passive"))
    )
    (net (code "175") (name "Net-(U13-RXD)") (class "Default")
      (node (ref "R64") (pin "1") (pinfunction "1_1") (pintype "passive"))
      (node (ref "U13") (pin "3") (pinfunction "RXD_3") (pintype "passive"))
    )
    (net (code "176") (name "Net-(U13-TXD)") (class "Default")
      (node (ref "R65") (pin "1") (pinfunction "1_1") (pintype "passive"))
      (node (ref "U13") (pin "2") (pinfunction "TXD_2") (pintype "passive"))
    )
    (net (code "177") (name "Net-(U13-V3)") (class "Default")
      (node (ref "C47") (pin "1") (pinfunction "1_1") (pintype "passive"))
      (node (ref "U13") (pin "4") (pinfunction "V3_4") (pintype "passive"))
    )
    (net (code "178") (name "Net-(U13-XI)") (class "Default")
      (node (ref "C51") (pin "2") (pinfunction "2_2") (pintype "passive"))
      (node (ref "U13") (pin "7") (pinfunction "XI_7") (pintype "passive"))
      (node (ref "Y3") (pin "1") (pinfunction "1_1") (pintype "passive"))
    )
    (net (code "179") (name "Net-(U13-XO)") (class "Default")
      (node (ref "C52") (pin "2") (pinfunction "2_2") (pintype "passive"))
      (node (ref "U13") (pin "8") (pinfunction "XO_8") (pintype "passive"))
      (node (ref "Y3") (pin "2") (pinfunction "2_2") (pintype "passive"))
    )
    (net (code "180") (name "Net-(U15-CANH)") (class "Default")
      (node (ref "CAN") (pin "1") (pinfunction "1_1") (pintype "passive"))
      (node (ref "R81") (pin "1") (pinfunction "1_1") (pintype "passive"))
      (node (ref "U15") (pin "7") (pinfunction "CANH_7") (pintype "bidirectional"))
    )
    (net (code "181") (name "Net-(U15-CANL)") (class "Default")
      (node (ref "CAN") (pin "2") (pinfunction "2_2") (pintype "passive"))
      (node (ref "R81") (pin "2") (pinfunction "2_2") (pintype "passive"))
      (node (ref "U15") (pin "6") (pinfunction "CANL_6") (pintype "bidirectional"))
    )
    (net (code "182") (name "Net-(USB-DM)") (class "Default")
      (node (ref "R9") (pin "1") (pinfunction "1_1") (pintype "passive"))
      (node (ref "USB") (pin "2") (pinfunction "DM_2") (pintype "passive"))
    )
    (net (code "183") (name "Net-(USB-DP)") (class "Default")
      (node (ref "R10") (pin "1") (pinfunction "1_1") (pintype "passive"))
      (node (ref "USB") (pin "3") (pinfunction "DP_3") (pintype "passive"))
    )
    (net (code "184") (name "Net-(USB2-DM)") (class "Default")
      (node (ref "R41") (pin "1") (pinfunction "1_1") (pintype "passive"))
      (node (ref "USB2") (pin "2") (pinfunction "DM_2") (pintype "passive"))
    )
    (net (code "185") (name "Net-(USB2-DP)") (class "Default")
      (node (ref "R42") (pin "1") (pinfunction "1_1") (pintype "passive"))
      (node (ref "USB2") (pin "3") (pinfunction "DP_3") (pintype "passive"))
    )
    (net (code "186") (name "Net-(USB2-VDD)") (class "Default")
      (node (ref "FUSE") (pin "1") (pinfunction "1_1") (pintype "passive"))
      (node (ref "USB2") (pin "1") (pinfunction "VDD_1") (pintype "passive"))
    )
    (net (code "187") (name "USIM_VDD") (class "Default")
      (node (ref "C15") (pin "1") (pinfunction "1_1") (pintype "passive"))
      (node (ref "R14") (pin "2") (pinfunction "2_2") (pintype "passive"))
      (node (ref "SIM") (pin "1") (pinfunction "VCC_1") (pintype "passive"))
      (node (ref "U5") (pin "8") (pinfunction "EC20_USIM_VDD/7600CE_USIM_VDD_8") (pintype "passive"))
      (node (ref "U6") (pin "5") (pintype "passive"))
    )
    (net (code "188") (name "VCC_1.8V") (class "Default")
      (node (ref "C10") (pin "1") (pinfunction "1_1") (pintype "passive"))
      (node (ref "C21") (pin "1") (pinfunction "1_1") (pintype "passive"))
      (node (ref "R82") (pin "1") (pinfunction "1_1") (pintype "passive"))
      (node (ref "U12") (pin "5") (pinfunction "VOUT_5") (pintype "passive"))
      (node (ref "U7") (pin "1") (pinfunction "VCCA_1") (pintype "passive"))
      (node (ref "U7") (pin "8") (pinfunction "OE_8") (pintype "passive"))
    )
    (net (code "189") (name "VCC_3.3V") (class "Default")
      (node (ref "C22") (pin "1") (pinfunction "1_1") (pintype "passive"))
      (node (ref "C23") (pin "2") (pinfunction "2_2") (pintype "passive"))
      (node (ref "C24") (pin "2") (pinfunction "2_2") (pintype "passive"))
      (node (ref "C25") (pin "2") (pinfunction "2_2") (pintype "passive"))
      (node (ref "C26") (pin "2") (pinfunction "2_2") (pintype "passive"))
      (node (ref "C27") (pin "2") (pinfunction "2_2") (pintype "passive"))
      (node (ref "C28") (pin "2") (pinfunction "2_2") (pintype "passive"))
      (node (ref "C29") (pin "2") (pinfunction "2_2") (pintype "passive"))
      (node (ref "C30") (pin "2") (pinfunction "2_2") (pintype "passive"))
      (node (ref "C31") (pin "2") (pinfunction "2_2") (pintype "passive"))
      (node (ref "C32") (pin "2") (pinfunction "2_2") (pintype "passive"))
      (node (ref "C33") (pin "2") (pinfunction "2_2") (pintype "passive"))
      (node (ref "C34") (pin "2") (pinfunction "2_2") (pintype "passive"))
      (node (ref "C35") (pin "2") (pinfunction "2_2") (pintype "passive"))
      (node (ref "C36") (pin "1") (pinfunction "1_1") (pintype "passive"))
      (node (ref "C37") (pin "1") (pinfunction "1_1") (pintype "passive"))
      (node (ref "C43") (pin "2") (pinfunction "2_2") (pintype "passive"))
      (node (ref "C44") (pin "2") (pinfunction "2_2") (pintype "passive"))
      (node (ref "C45") (pin "1") (pinfunction "1_1") (pintype "passive"))
      (node (ref "C55") (pin "2") (pinfunction "2_2") (pintype "passive"))
      (node (ref "C77") (pin "2") (pinfunction "2_2") (pintype "passive"))
      (node (ref "DHT11") (pin "1") (pinfunction "VCC_1") (pintype "passive"))
      (node (ref "JTAG") (pin "1") (pinfunction "VCC_1") (pintype "passive"))
      (node (ref "JTAG") (pin "2") (pinfunction "VCC_2") (pintype "passive"))
      (node (ref "LCD") (pin "24") (pinfunction "VDD3.3_24") (pintype "passive"))
      (node (ref "LCD") (pin "25") (pinfunction "VDD3.3_25") (pintype "passive"))
      (node (ref "OV2640") (pin "1") (pinfunction "1_1") (pintype "passive"))
      (node (ref "Q4") (pin "3") (pinfunction "C_3") (pintype "passive"))
      (node (ref "R18") (pin "2") (pinfunction "2_2") (pintype "passive"))
      (node (ref "R19") (pin "1") (pinfunction "1_1") (pintype "passive"))
      (node (ref "R28") (pin "1") (pinfunction "1_1") (pintype "passive"))
      (node (ref "R31") (pin "1") (pinfunction "1_1") (pintype "passive"))
      (node (ref "R32") (pin "2") (pinfunction "2_2") (pintype "passive"))
      (node (ref "R34") (pin "2") (pinfunction "2_2") (pintype "passive"))
      (node (ref "R35") (pin "2") (pinfunction "2_2") (pintype "passive"))
      (node (ref "R44") (pin "1") (pinfunction "1_1") (pintype "passive"))
      (node (ref "R47") (pin "1") (pinfunction "1_1") (pintype "passive"))
      (node (ref "R55") (pin "2") (pinfunction "2_2") (pintype "passive"))
      (node (ref "R56") (pin "2") (pinfunction "2_2") (pintype "passive"))
      (node (ref "R57") (pin "2") (pinfunction "2_2") (pintype "passive"))
      (node (ref "R58") (pin "2") (pinfunction "2_2") (pintype "passive"))
      (node (ref "R59") (pin "2") (pinfunction "2_2") (pintype "passive"))
      (node (ref "R60") (pin "1") (pinfunction "1_1") (pintype "passive"))
      (node (ref "R62") (pin "1") (pinfunction "1_1") (pintype "passive"))
      (node (ref "R63") (pin "1") (pinfunction "1_1") (pintype "passive"))
      (node (ref "R70") (pin "1") (pinfunction "1_1") (pintype "passive"))
      (node (ref "R71") (pin "1") (pinfunction "1_1") (pintype "passive"))
      (node (ref "R83") (pin "1") (pinfunction "1_1") (pintype "passive"))
      (node (ref "TVS1") (pin "2") (pinfunction "K_2") (pintype "passive"))
      (node (ref "U10") (pin "11") (pinfunction "VDD_11") (pintype "passive"))
      (node (ref "U10") (pin "33") (pinfunction "VDD_33") (pintype "passive"))
      (node (ref "U11") (pin "8") (pinfunction "VCC_8") (pintype "passive"))
      (node (ref "U12") (pin "1") (pinfunction "VIN_1") (pintype "passive"))
      (node (ref "U12") (pin "3") (pinfunction "EN_3") (pintype "passive"))
      (node (ref "U3") (pin "2") (pinfunction "Vout_2") (pintype "passive"))
      (node (ref "U3") (pin "4") (pinfunction "Vout2_4") (pintype "power_in"))
      (node (ref "U4") (pin "8") (pinfunction "VCC_8") (pintype "passive"))
      (node (ref "U7") (pin "14") (pinfunction "VCCB_14") (pintype "passive"))
      (node (ref "U8") (pin "108") (pinfunction "VDD_108") (pintype "passive"))
      (node (ref "U8") (pin "121") (pinfunction "VDD_121") (pintype "passive"))
      (node (ref "U8") (pin "131") (pinfunction "VDD_131") (pintype "passive"))
      (node (ref "U8") (pin "144") (pinfunction "VDD_144") (pintype "passive"))
      (node (ref "U8") (pin "17") (pinfunction "VDD_17") (pintype "passive"))
      (node (ref "U8") (pin "30") (pinfunction "VDD_30") (pintype "passive"))
      (node (ref "U8") (pin "39") (pinfunction "VDD_39") (pintype "passive"))
      (node (ref "U8") (pin "52") (pinfunction "VDD_52") (pintype "passive"))
      (node (ref "U8") (pin "6") (pinfunction "VBAT_6") (pintype "passive"))
      (node (ref "U8") (pin "62") (pinfunction "VDD_62") (pintype "passive"))
      (node (ref "U8") (pin "72") (pinfunction "VDD_72") (pintype "passive"))
      (node (ref "U8") (pin "84") (pinfunction "VDD_84") (pintype "passive"))
      (node (ref "U8") (pin "95") (pinfunction "VDD_95") (pintype "passive"))
      (node (ref "U9") (pin "7") (pinfunction "HOLD_7") (pintype "passive"))
      (node (ref "U9") (pin "8") (pinfunction "VCC_8") (pintype "passive"))
    )
    (net (code "190") (name "VCC_3.8V") (class "Default")
      (node (ref "C120") (pin "2") (pinfunction "2_2") (pintype "passive"))
      (node (ref "C17") (pin "2") (pinfunction "2_2") (pintype "passive"))
      (node (ref "C18") (pin "2") (pinfunction "2_2") (pintype "passive"))
      (node (ref "C19") (pin "2") (pinfunction "2_2") (pintype "passive"))
      (node (ref "C20") (pin "2") (pinfunction "2_2") (pintype "passive"))
      (node (ref "C4") (pin "1") (pinfunction "1_1") (pintype "passive"))
      (node (ref "C5") (pin "2") (pinfunction "2_2") (pintype "passive"))
      (node (ref "R15") (pin "2") (pinfunction "2_2") (pintype "passive"))
      (node (ref "R22") (pin "2") (pinfunction "2_2") (pintype "passive"))
      (node (ref "R4") (pin "1") (pinfunction "1_1") (pintype "passive"))
      (node (ref "R6") (pin "1") (pinfunction "1_1") (pintype "passive"))
      (node (ref "TVS2") (pin "2") (pinfunction "K_2") (pintype "passive"))
      (node (ref "U2") (pin "4") (pinfunction "OUT_4") (pintype "passive"))
      (node (ref "U5") (pin "2") (pinfunction "VBAT_2") (pintype "passive"))
      (node (ref "U5") (pin "24") (pinfunction "VBAT_24") (pintype "passive"))
      (node (ref "U5") (pin "39") (pinfunction "VBAT_39") (pintype "passive"))
      (node (ref "U5") (pin "41") (pinfunction "VBAT_41") (pintype "passive"))
      (node (ref "U5") (pin "52") (pinfunction "VBAT_52") (pintype "passive"))
    )
    (net (code "191") (name "VCC_5V") (class "Default")
      (node (ref "C2") (pin "1") (pinfunction "1_1") (pintype "passive"))
      (node (ref "C3") (pin "2") (pinfunction "2_2") (pintype "passive"))
      (node (ref "C48") (pin "1") (pinfunction "1_1") (pintype "passive"))
      (node (ref "C49") (pin "1") (pinfunction "1_1") (pintype "passive"))
      (node (ref "C50") (pin "2") (pinfunction "2_2") (pintype "passive"))
      (node (ref "C54") (pin "2") (pinfunction "2_2") (pintype "passive"))
      (node (ref "C61") (pin "2") (pinfunction "2_2") (pintype "passive"))
      (node (ref "FUSE") (pin "2") (pinfunction "2_2") (pintype "passive"))
      (node (ref "L1") (pin "2") (pinfunction "2_2") (pintype "passive"))
      (node (ref "LCD") (pin "28") (pinfunction "BL_VDD_28") (pintype "passive"))
      (node (ref "R1") (pin "1") (pinfunction "1_1") (pintype "passive"))
      (node (ref "TVS3") (pin "2") (pinfunction "K_2") (pintype "passive"))
      (node (ref "U1") (pin "4") (pinfunction "FeedBack_4") (pintype "passive"))
      (node (ref "U13") (pin "16") (pinfunction "VCC_16") (pintype "passive"))
      (node (ref "U15") (pin "3") (pinfunction "VCC_3") (pintype "power_in"))
      (node (ref "U2") (pin "2") (pinfunction "IN_2") (pintype "passive"))
      (node (ref "U3") (pin "3") (pinfunction "Vin_3") (pintype "passive"))
    )
    (net (code "192") (name "VCC_12V") (class "Default")
      (node (ref "C1") (pin "1") (pinfunction "1_1") (pintype "passive"))
      (node (ref "Q7") (pin "2") (pinfunction "S_2") (pintype "passive"))
      (node (ref "R52") (pin "2") (pinfunction "2_2") (pintype "passive"))
      (node (ref "S1") (pin "1") (pinfunction "1_1") (pintype "passive"))
      (node (ref "U1") (pin "1") (pinfunction "VIN_1") (pintype "passive"))
    )
    (net (code "193") (name "VCC_IN") (class "Default")
      (node (ref "D4") (pin "2") (pinfunction "K_2") (pintype "passive"))
      (node (ref "JP1") (pin "1") (pinfunction "1_1") (pintype "passive"))
      (node (ref "S1") (pin "2") (pinfunction "2_2") (pintype "passive"))
    )
    (net (code "194") (name "unconnected-(JTAG-NC-Pad17)") (class "Default")
      (node (ref "JTAG") (pin "17") (pinfunction "NC_17") (pintype "passive"))
    )
    (net (code "195") (name "unconnected-(JTAG-NC-Pad19)") (class "Default")
      (node (ref "JTAG") (pin "19") (pinfunction "NC_19") (pintype "passive"))
    )
    (net (code "196") (name "unconnected-(LCD-MO-Pad32)") (class "Default")
      (node (ref "LCD") (pin "32") (pinfunction "MO_32") (pintype "passive"))
    )
    (net (code "197") (name "unconnected-(S1-Pad3)") (class "Default")
      (node (ref "S1") (pin "3") (pinfunction "3_3") (pintype "passive"))
    )
    (net (code "198") (name "unconnected-(S1-Pad4)") (class "Default")
      (node (ref "S1") (pin "4") (pinfunction "4_4") (pintype "passive"))
    )
    (net (code "199") (name "unconnected-(S1-Pad4)_1") (class "Default")
      (node (ref "S1") (pin "4") (pinfunction "4_4") (pintype "passive"))
    )
    (net (code "200") (name "unconnected-(SIM-VPP-Pad5)") (class "Default")
      (node (ref "SIM") (pin "5") (pinfunction "VPP_5") (pintype "passive"))
    )
    (net (code "201") (name "unconnected-(U4-Inputs_B+-Pad5)") (class "Default")
      (node (ref "U4") (pin "5") (pinfunction "Inputs_B+_5") (pintype "passive"))
    )
    (net (code "202") (name "unconnected-(U4-Inputs_B--Pad6)") (class "Default")
      (node (ref "U4") (pin "6") (pinfunction "Inputs_B-_6") (pintype "passive"))
    )
    (net (code "203") (name "unconnected-(U4-Output_B-Pad7)") (class "Default")
      (node (ref "U4") (pin "7") (pinfunction "Output_B_7") (pintype "passive"))
    )
    (net (code "204") (name "unconnected-(U5-EC20_MIC_N*{slash}7600CE_MIC_N*-Pad3)") (class "Default")
      (node (ref "U5") (pin "3") (pinfunction "EC20_MIC_N*/7600CE_MIC_N*_3") (pintype "passive"))
    )
    (net (code "205") (name "unconnected-(U5-EC20_MIC_P*{slash}7600CE_MIC_P*-Pad1)") (class "Default")
      (node (ref "U5") (pin "1") (pinfunction "EC20_MIC_P*/7600CE_MIC_P*_1") (pintype "passive"))
    )
    (net (code "206") (name "unconnected-(U5-EC20_NC{slash}7600CE_NC-Pad6)") (class "Default")
      (node (ref "U5") (pin "6") (pinfunction "EC20_NC/7600CE_NC_6") (pintype "passive"))
    )
    (net (code "207") (name "unconnected-(U5-EC20_NC{slash}7600CE_NC-Pad48)") (class "Default")
      (node (ref "U5") (pin "48") (pinfunction "EC20_NC/7600CE_NC_48") (pintype "passive"))
    )
    (net (code "208") (name "unconnected-(U5-EC20_PERST1#{slash}7600CE_NC-Pad33)") (class "Default")
      (node (ref "U5") (pin "33") (pinfunction "EC20_PERST1#/7600CE_NC_33") (pintype "passive"))
    )
    (net (code "209") (name "unconnected-(U5-EC20_RESERVED{slash}7600CE_NC-Pad45)") (class "Default")
      (node (ref "U5") (pin "45") (pinfunction "EC20_RESERVED/7600CE_NC_45") (pintype "passive"))
    )
    (net (code "210") (name "unconnected-(U5-EC20_RESERVED{slash}7600CE_NC-Pad47)") (class "Default")
      (node (ref "U5") (pin "47") (pinfunction "EC20_RESERVED/7600CE_NC_47") (pintype "passive"))
    )
    (net (code "211") (name "unconnected-(U5-EC20_RESERVED{slash}7600CE_NC-Pad49)") (class "Default")
      (node (ref "U5") (pin "49") (pinfunction "EC20_RESERVED/7600CE_NC_49") (pintype "passive"))
    )
    (net (code "212") (name "unconnected-(U5-EC20_RESERVED{slash}7600CE_NC-Pad51)") (class "Default")
      (node (ref "U5") (pin "51") (pinfunction "EC20_RESERVED/7600CE_NC_51") (pintype "passive"))
    )
    (net (code "213") (name "unconnected-(U5-EC20_RESERVED{slash}7600CE_UART_RI-Pad44)") (class "Default")
      (node (ref "U5") (pin "44") (pinfunction "EC20_RESERVED/7600CE_UART_RI_44") (pintype "passive"))
    )
    (net (code "214") (name "unconnected-(U5-EC20_RESERVED{slash}7600CE_USIM_DET-Pad16)") (class "Default")
      (node (ref "U5") (pin "16") (pinfunction "EC20_RESERVED/7600CE_USIM_DET_16") (pintype "passive"))
    )
    (net (code "215") (name "unconnected-(U5-EC20_SPK_N*{slash}7600CE_SPK_N*-Pad7)") (class "Default")
      (node (ref "U5") (pin "7") (pinfunction "EC20_SPK_N*/7600CE_SPK_N*_7") (pintype "passive"))
    )
    (net (code "216") (name "unconnected-(U5-EC20_SPK_P*{slash}7600CE_SPK_P*-Pad5)") (class "Default")
      (node (ref "U5") (pin "5") (pinfunction "EC20_SPK_P*/7600CE_SPK_P*_5") (pintype "passive"))
    )
    (net (code "217") (name "unconnected-(U5-EC20_UART_DCD{slash}7600CE_SCL-Pad30)") (class "Default")
      (node (ref "U5") (pin "30") (pinfunction "EC20_UART_DCD/7600CE_SCL_30") (pintype "passive"))
    )
    (net (code "218") (name "unconnected-(U5-EC20_UART_DTR{slash}7600CE_UART_DTR-Pad46)") (class "Default")
      (node (ref "U5") (pin "46") (pinfunction "EC20_UART_DTR/7600CE_UART_DTR_46") (pintype "passive"))
    )
    (net (code "219") (name "unconnected-(U5-EC20_WAKEUP_OUT{slash}7600CE_SDA-Pad32)") (class "Default")
      (node (ref "U5") (pin "32") (pinfunction "EC20_WAKEUP_OUT/7600CE_SDA_32") (pintype "passive"))
    )
    (net (code "220") (name "unconnected-(U5-EC20_W_DISABLE#{slash}7600CE_W_DISABLE#-Pad20)") (class "Default")
      (node (ref "U5") (pin "20") (pinfunction "EC20_W_DISABLE#/7600CE_W_DISABLE#_20") (pintype "passive"))
    )
    (net (code "221") (name "unconnected-(U6-A-Pad1)") (class "Default")
      (node (ref "U6") (pin "1") (pinfunction "A_1") (pintype "passive"))
    )
    (net (code "222") (name "unconnected-(U6-K-Pad2)") (class "Default")
      (node (ref "U6") (pin "2") (pinfunction "K_2") (pintype "passive"))
    )
    (net (code "223") (name "unconnected-(U6-Pad1)") (class "Default")
      (node (ref "U6") (pin "1") (pintype "passive"))
    )
    (net (code "224") (name "unconnected-(U7-NC-Pad6)") (class "Default")
      (node (ref "U7") (pin "6") (pinfunction "NC_6") (pintype "passive"))
    )
    (net (code "225") (name "unconnected-(U7-NC-Pad9)") (class "Default")
      (node (ref "U7") (pin "9") (pinfunction "NC_9") (pintype "passive"))
    )
    (net (code "226") (name "unconnected-(U8-PB5{slash}TIM3_CH2{slash}SPI1_MOSI{slash}SPI3_MOSI{slash}CAN2_RX{slash}I2C1_SMBA{slash}OTG_HS_ULPI_D7{slash}ETH_PPS_OUT{slash}DCMI_D10{slash}I2S3_SD-Pad135)") (class "Default")
      (node (ref "U8") (pin "135") (pinfunction "PB5/TIM3_CH2/SPI1_MOSI/SPI3_MOSI/CAN2_RX/I2C1_SMBA/OTG_HS_ULPI_D7/ETH_PPS_OUT/DCMI_D10/I2S3_SD_135") (pintype "passive"))
    )
    (net (code "227") (name "unconnected-(U8-PB8{slash}TIM4_CH3{slash}TIM10_CH1{slash}CAN1_RX{slash}SDIO_D4{slash}ETH_MII_TXD3{slash}I2C1_SCL{slash}DCMI_D6-Pad139)") (class "Default")
      (node (ref "U8") (pin "139") (pinfunction "PB8/TIM4_CH3/TIM10_CH1/CAN1_RX/SDIO_D4/ETH_MII_TXD3/I2C1_SCL/DCMI_D6_139") (pintype "passive"))
    )
    (net (code "228") (name "unconnected-(U8-PB9{slash}TIM4_CH4{slash}TIM11_CH1{slash}CAN1_TX{slash}SDIO_D5{slash}SPI2_NSS{slash}I2C1_SDA{slash}DCMI_D7{slash}I2S2_WS-Pad140)") (class "Default")
      (node (ref "U8") (pin "140") (pinfunction "PB9/TIM4_CH4/TIM11_CH1/CAN1_TX/SDIO_D5/SPI2_NSS/I2C1_SDA/DCMI_D7/I2S2_WS_140") (pintype "passive"))
    )
    (net (code "229") (name "unconnected-(U8-PC10{slash}SPI3_SCK{slash}U3_TX{slash}U4_TX{slash}SDIO_D2{slash}DCMI_D8{slash}I2S3_CK-Pad111)") (class "Default")
      (node (ref "U8") (pin "111") (pinfunction "PC10/SPI3_SCK/U3_TX/U4_TX/SDIO_D2/DCMI_D8/I2S3_CK_111") (pintype "passive"))
    )
    (net (code "230") (name "unconnected-(U8-PF6{slash}TIM10_CH1{slash}FSMC_NIORD{slash}ADC3_IN4-Pad18)") (class "Default")
      (node (ref "U8") (pin "18") (pinfunction "PF6/TIM10_CH1/FSMC_NIORD/ADC3_IN4_18") (pintype "passive"))
    )
    (net (code "231") (name "unconnected-(U8-PF7{slash}TIM11_CH1{slash}FSMC_NREG{slash}ADC3_IN5-Pad19)") (class "Default")
      (node (ref "U8") (pin "19") (pinfunction "PF7/TIM11_CH1/FSMC_NREG/ADC3_IN5_19") (pintype "passive"))
    )
    (net (code "232") (name "unconnected-(U8-PF8{slash}TIM13_CH1{slash}FSMC_NIOWR{slash}ADC3_IN6-Pad20)") (class "Default")
      (node (ref "U8") (pin "20") (pinfunction "PF8/TIM13_CH1/FSMC_NIOWR/ADC3_IN6_20") (pintype "passive"))
    )
    (net (code "233") (name "unconnected-(U8-PF9{slash}TIM14_CH1{slash}FSMC_CD{slash}ADC3_IN7-Pad21)") (class "Default")
      (node (ref "U8") (pin "21") (pinfunction "PF9/TIM14_CH1/FSMC_CD/ADC3_IN7_21") (pintype "passive"))
    )
    (net (code "234") (name "unconnected-(U8-PF10{slash}FSMC_INTR{slash}ADC3_IN8-Pad22)") (class "Default")
      (node (ref "U8") (pin "22") (pinfunction "PF10/FSMC_INTR/ADC3_IN8_22") (pintype "passive"))
    )
    (net (code "235") (name "unconnected-(U8-PG6{slash}FSMC_INT2-Pad91)") (class "Default")
      (node (ref "U8") (pin "91") (pinfunction "PG6/FSMC_INT2_91") (pintype "passive"))
    )
    (net (code "236") (name "unconnected-(U8-PG7{slash}FSMC_INT3{slash}U6_CK-Pad92)") (class "Default")
      (node (ref "U8") (pin "92") (pinfunction "PG7/FSMC_INT3/U6_CK_92") (pintype "passive"))
    )
    (net (code "237") (name "unconnected-(U8-PG8{slash}U6_RTS{slash}ETH_PPS_OUT-Pad93)") (class "Default")
      (node (ref "U8") (pin "93") (pinfunction "PG8/U6_RTS/ETH_PPS_OUT_93") (pintype "passive"))
    )
    (net (code "238") (name "unconnected-(U8-PG11{slash}FSMC_NCE4_2{slash}ETH_MII_TX_EN{slash}ETH_RMII_TX_EN-Pad126)") (class "Default")
      (node (ref "U8") (pin "126") (pinfunction "PG11/FSMC_NCE4_2/ETH_MII_TX_EN/ETH_RMII_TX_EN_126") (pintype "passive"))
    )
    (net (code "239") (name "unconnected-(U8-PG13{slash}FSMC_A24{slash}U6_CTS{slash}ETH_MII_TXD0{slash}ETH_RMII_TXD0-Pad128)") (class "Default")
      (node (ref "U8") (pin "128") (pinfunction "PG13/FSMC_A24/U6_CTS/ETH_MII_TXD0/ETH_RMII_TXD0_128") (pintype "passive"))
    )
    (net (code "240") (name "unconnected-(U8-PG14{slash}FSMC_A25{slash}U6_TX{slash}ETH_MII_TXD1{slash}ETH_RMII_TXD1-Pad129)") (class "Default")
      (node (ref "U8") (pin "129") (pinfunction "PG14/FSMC_A25/U6_TX/ETH_MII_TXD1/ETH_RMII_TXD1_129") (pintype "passive"))
    )
    (net (code "241") (name "unconnected-(U13-CTS-Pad9)") (class "Default")
      (node (ref "U13") (pin "9") (pinfunction "CTS_9") (pintype "passive"))
    )
    (net (code "242") (name "unconnected-(U13-DCD-Pad12)") (class "Default")
      (node (ref "U13") (pin "12") (pinfunction "DCD_12") (pintype "passive"))
    )
    (net (code "243") (name "unconnected-(U13-DSR-Pad10)") (class "Default")
      (node (ref "U13") (pin "10") (pinfunction "DSR_10") (pintype "passive"))
    )
    (net (code "244") (name "unconnected-(U13-R232-Pad15)") (class "Default")
      (node (ref "U13") (pin "15") (pinfunction "R232_15") (pintype "passive"))
    )
    (net (code "245") (name "unconnected-(U13-RI-Pad11)") (class "Default")
      (node (ref "U13") (pin "11") (pinfunction "RI_11") (pintype "passive"))
    )
    (net (code "246") (name "unconnected-(U15-Vref-Pad5)") (class "Default")
      (node (ref "U15") (pin "5") (pinfunction "Vref_5") (pintype "output"))
    )
    (net (code "247") (name "unconnected-(USB-NC-Pad4)") (class "Default")
      (node (ref "USB") (pin "4") (pinfunction "NC_4") (pintype "passive"))
    )
    (net (code "248") (name "unconnected-(USB-VDD-Pad1)") (class "Default")
      (node (ref "USB") (pin "1") (pinfunction "VDD_1") (pintype "passive"))
    )
    (net (code "249") (name "unconnected-(USB2-NC-Pad4)") (class "Default")
      (node (ref "USB2") (pin "4") (pinfunction "NC_4") (pintype "passive"))
    )
  )
)
